# dw08b.net
KiCad netlist of a schematic drawn in EAGLE
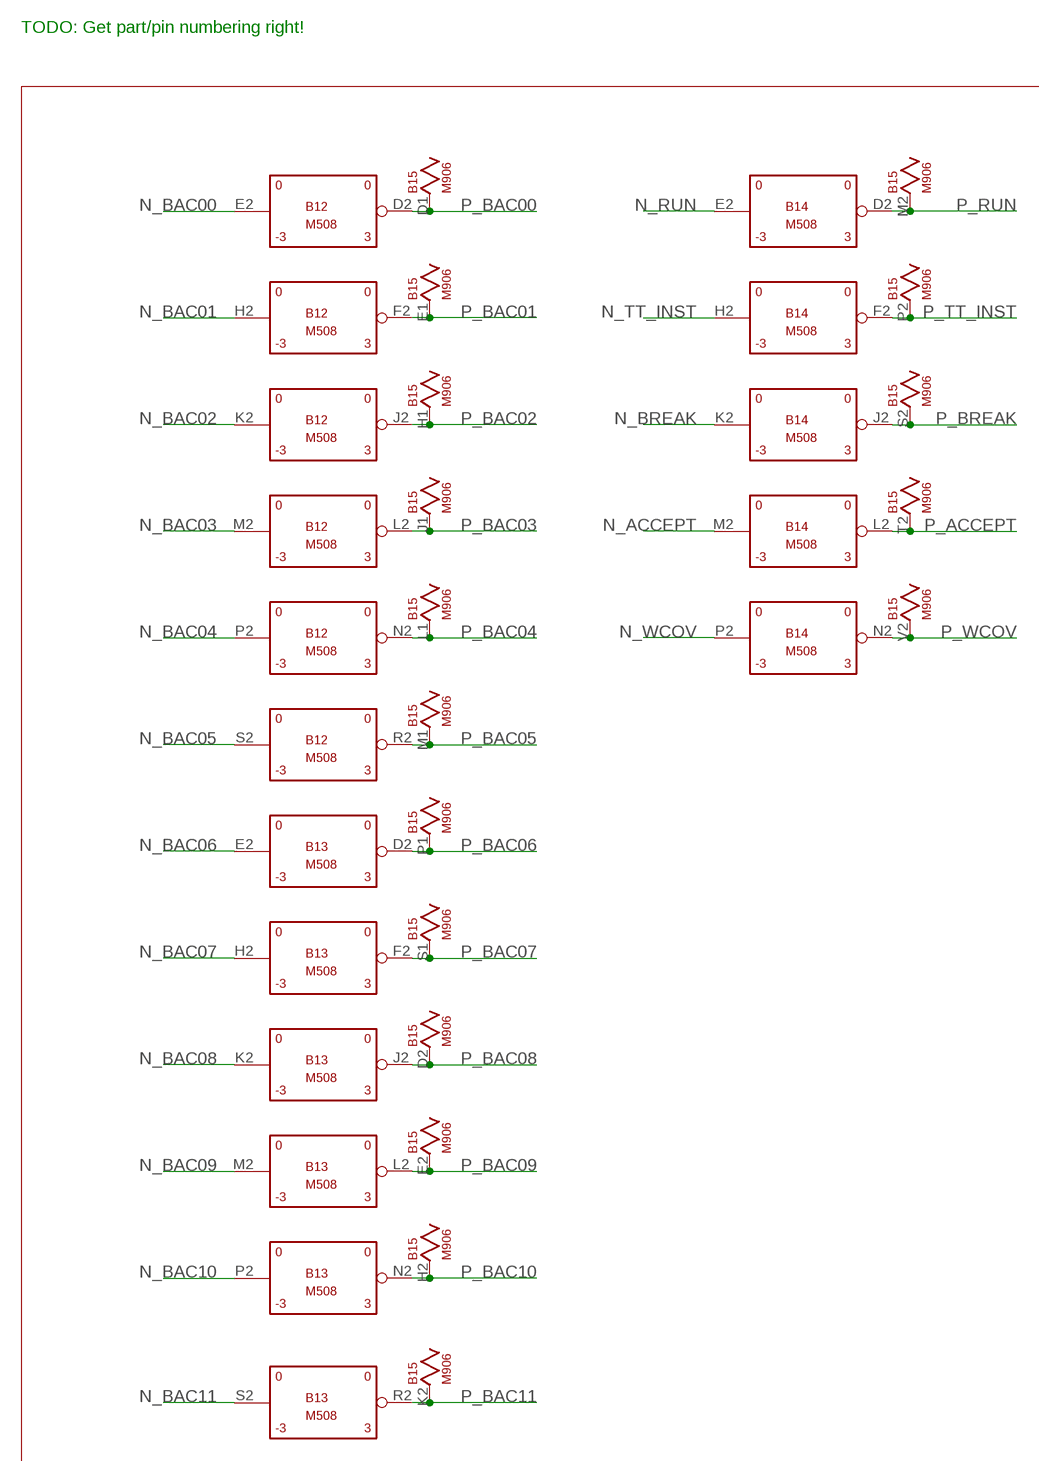
[diagram p0: schematic, sheet 1, part 1 of 2]
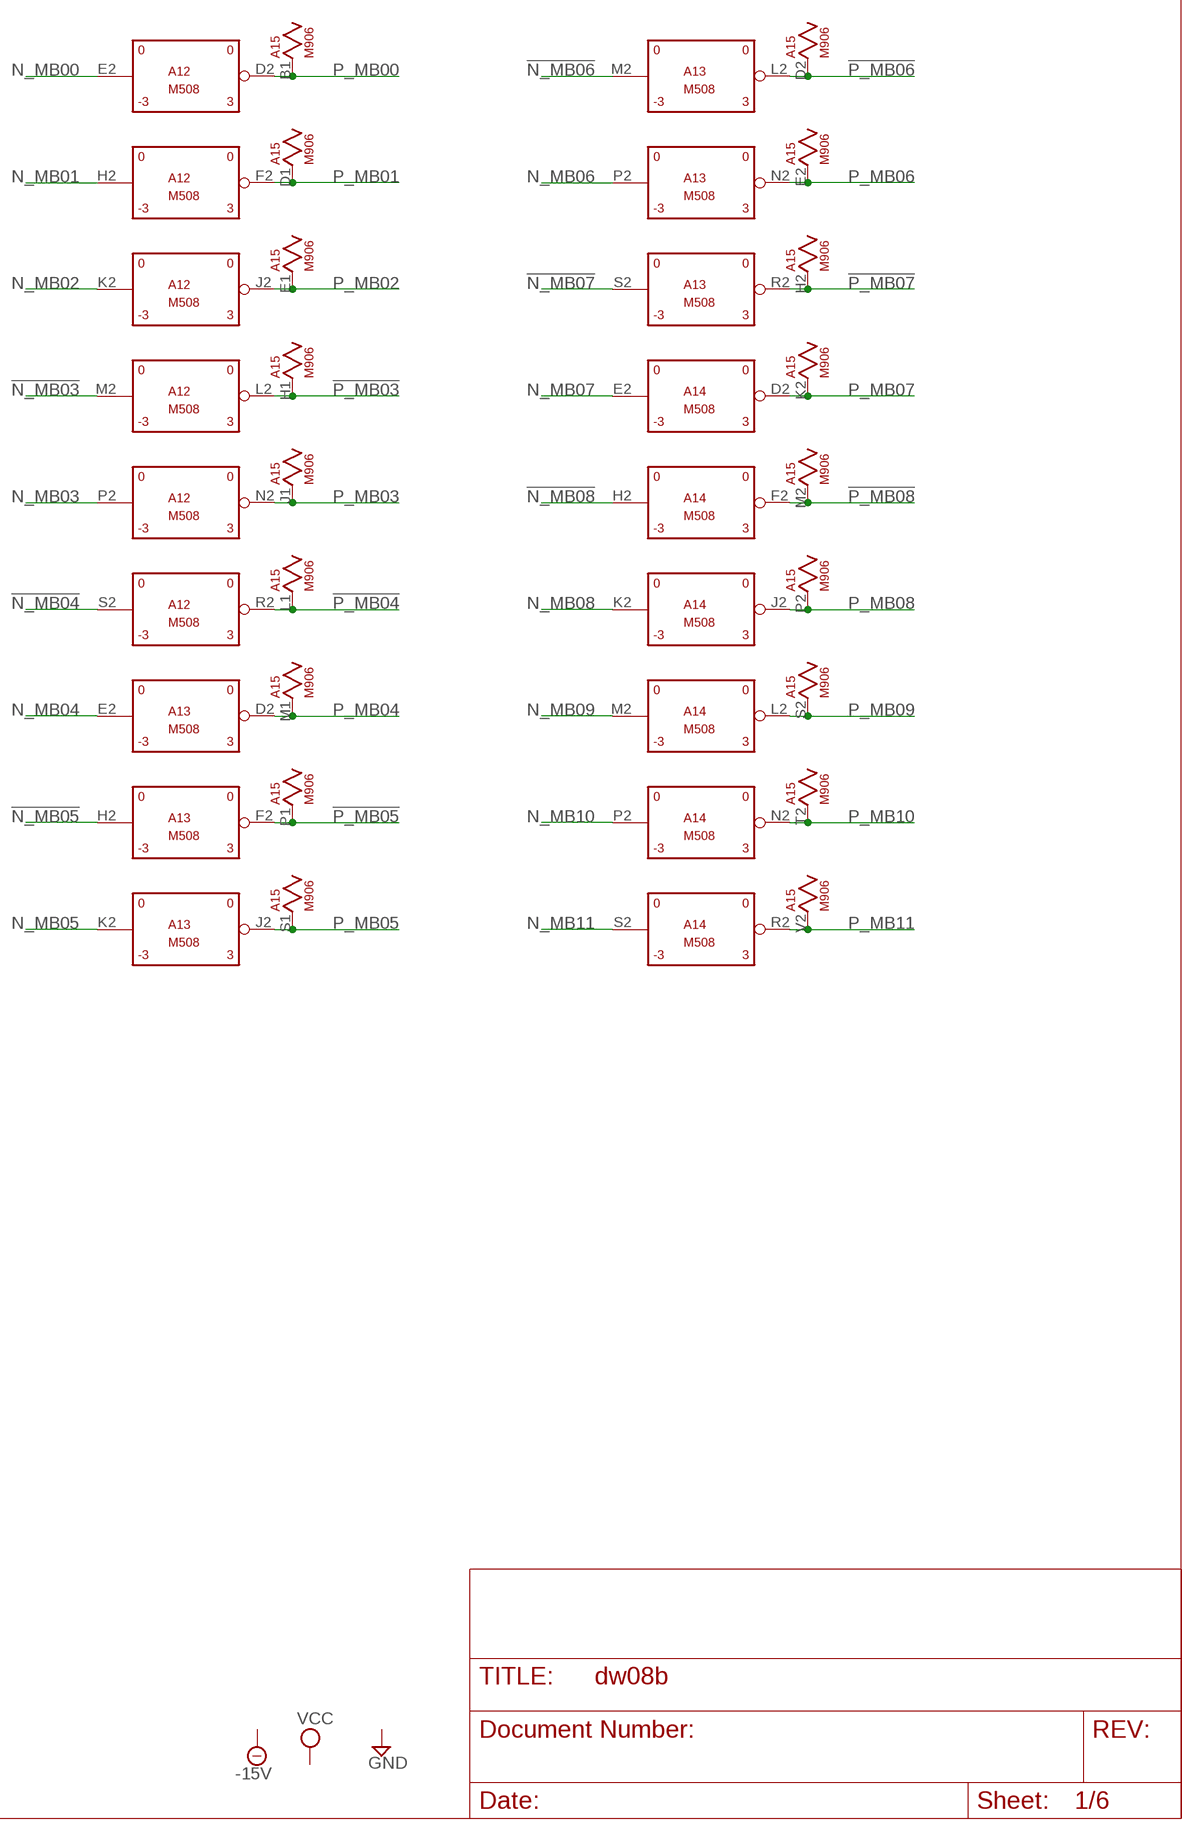
[diagram p1: schematic, sheet 1, part 2 of 2]
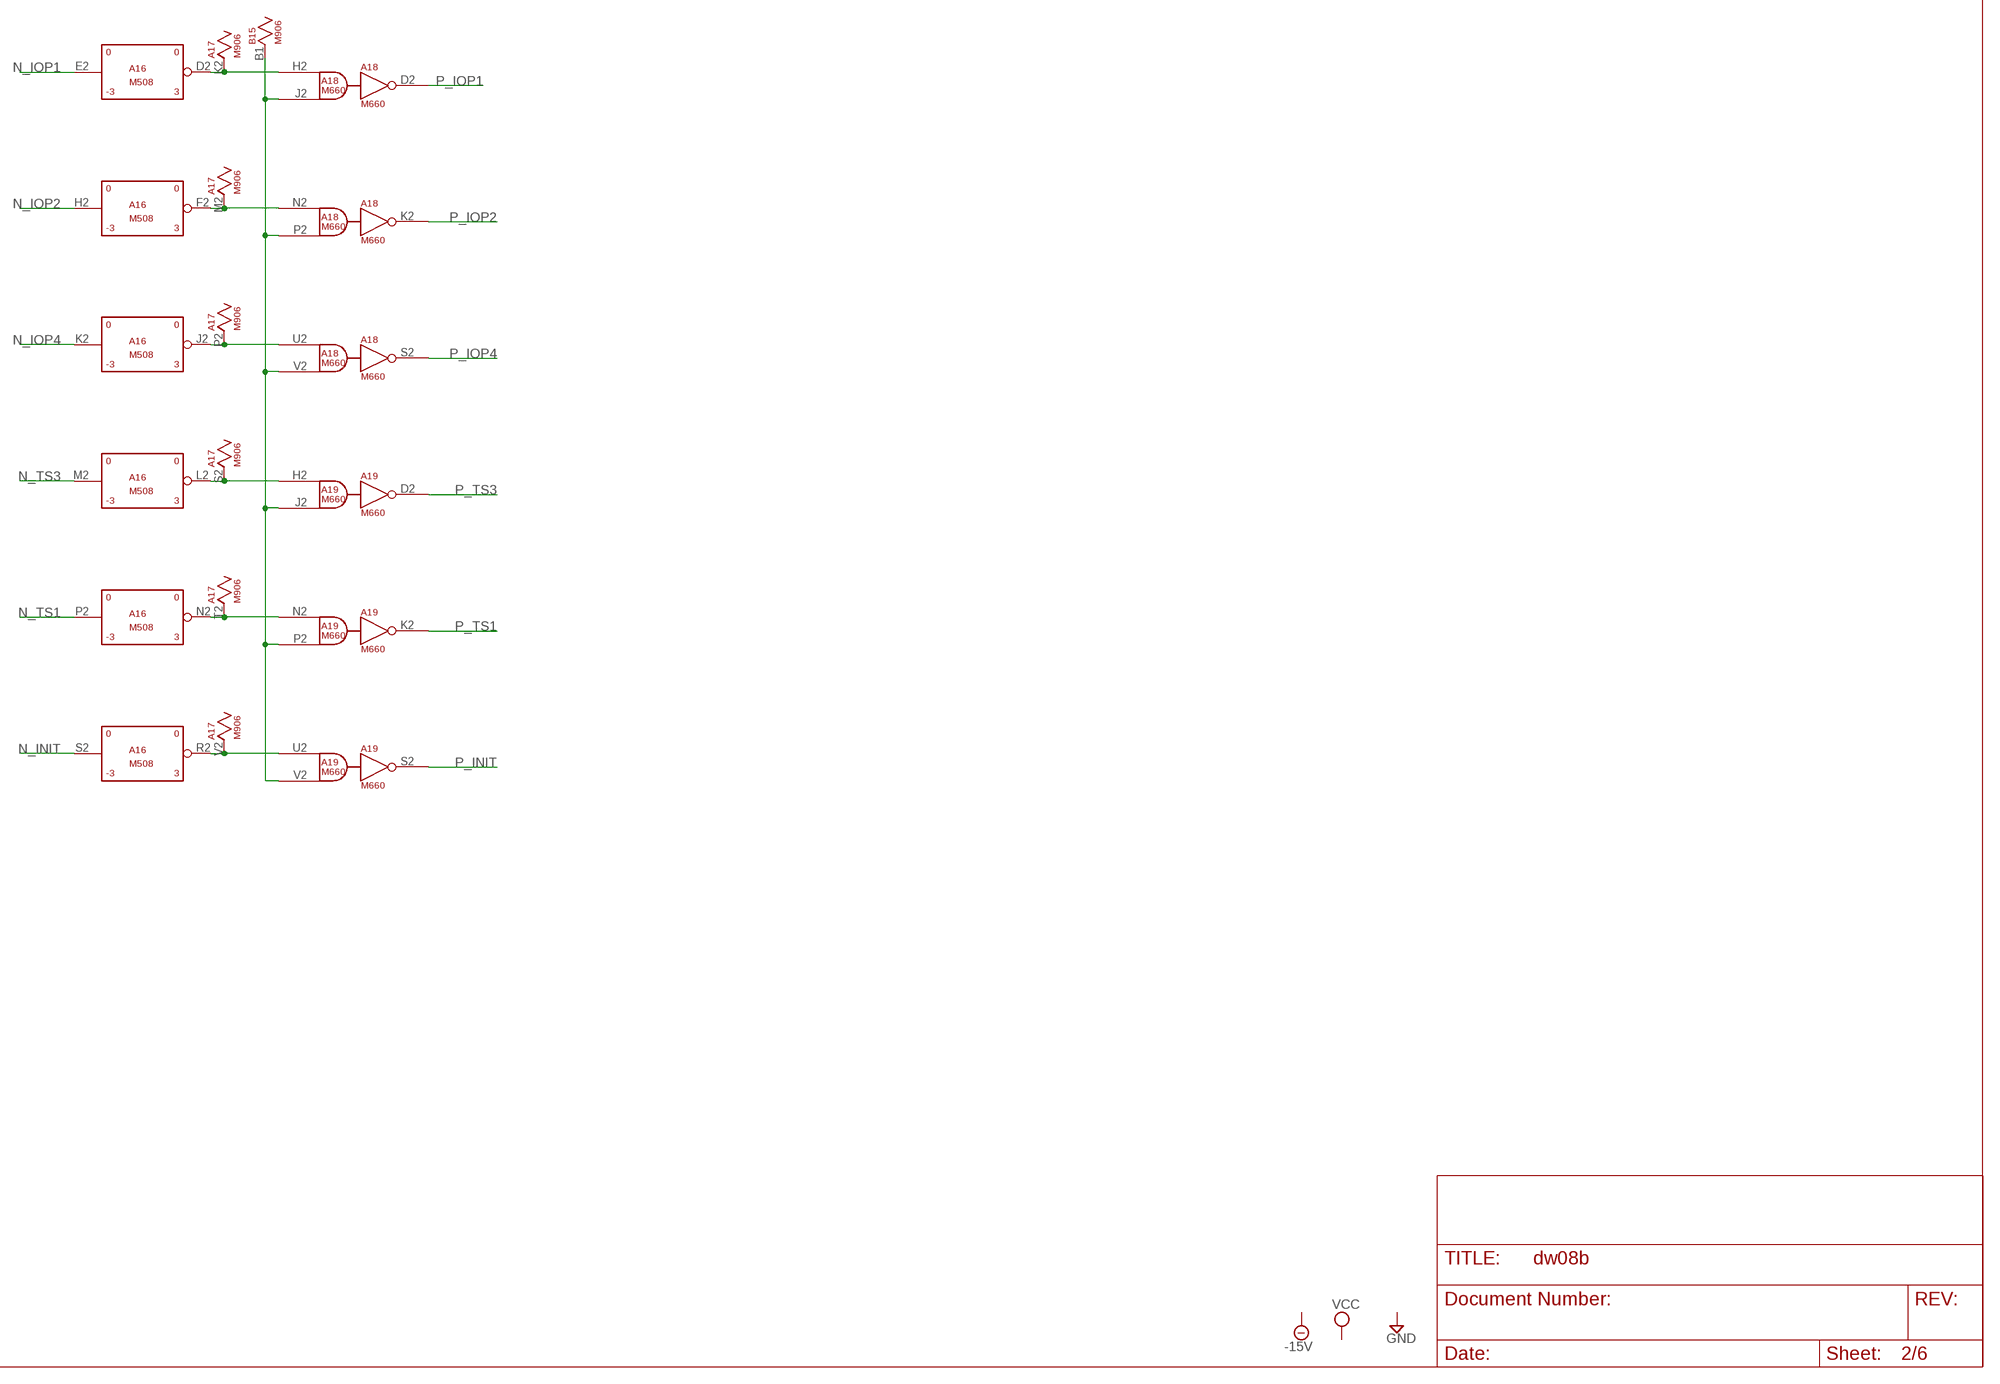
[diagram p2: schematic, sheet 2]
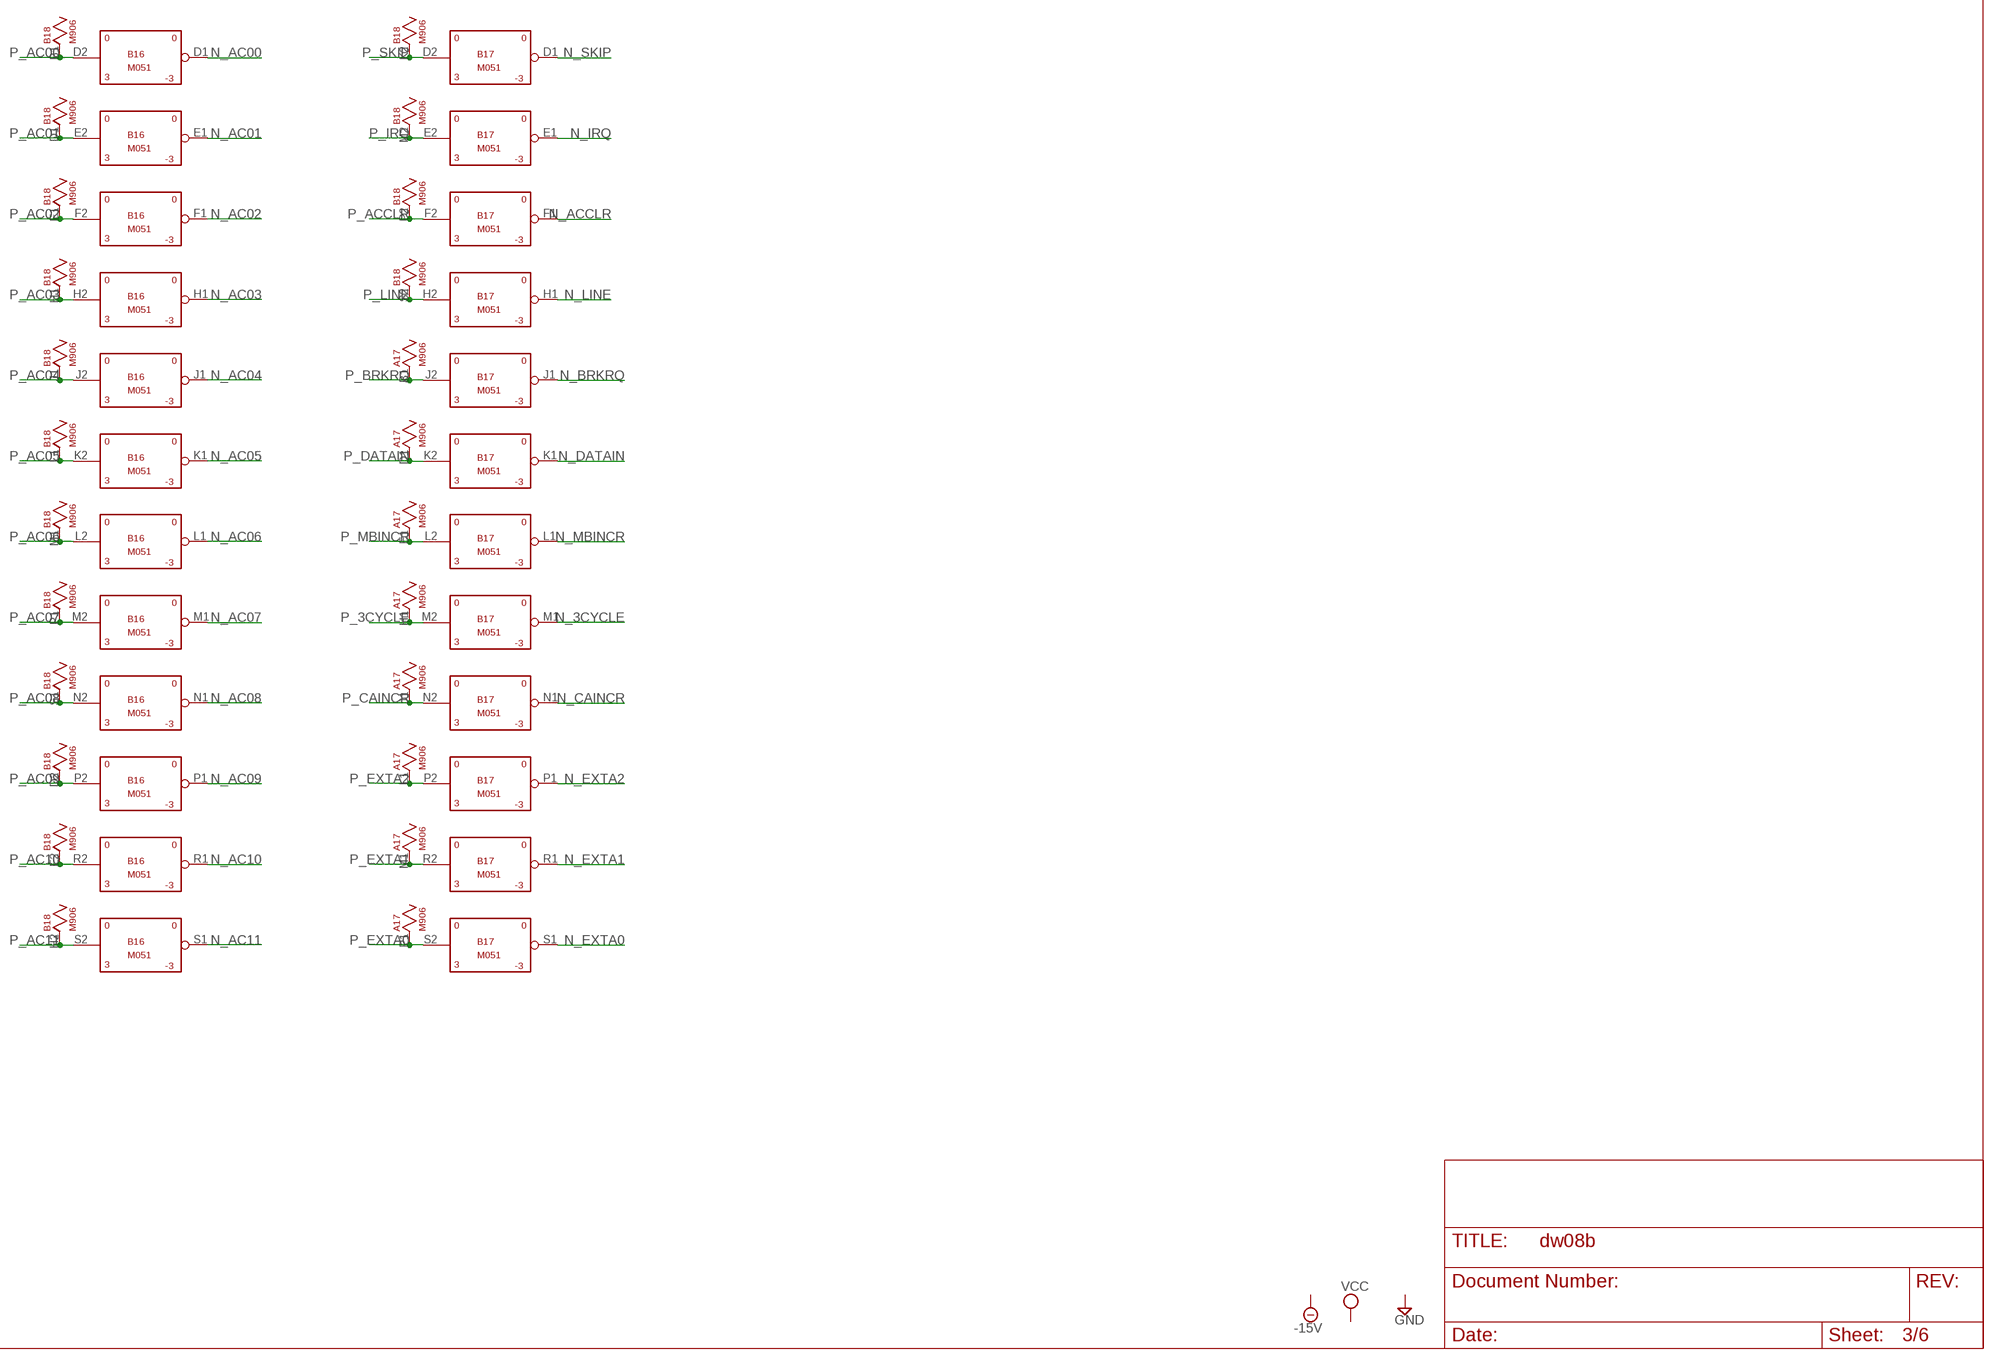
[diagram p3: schematic, sheet 3]
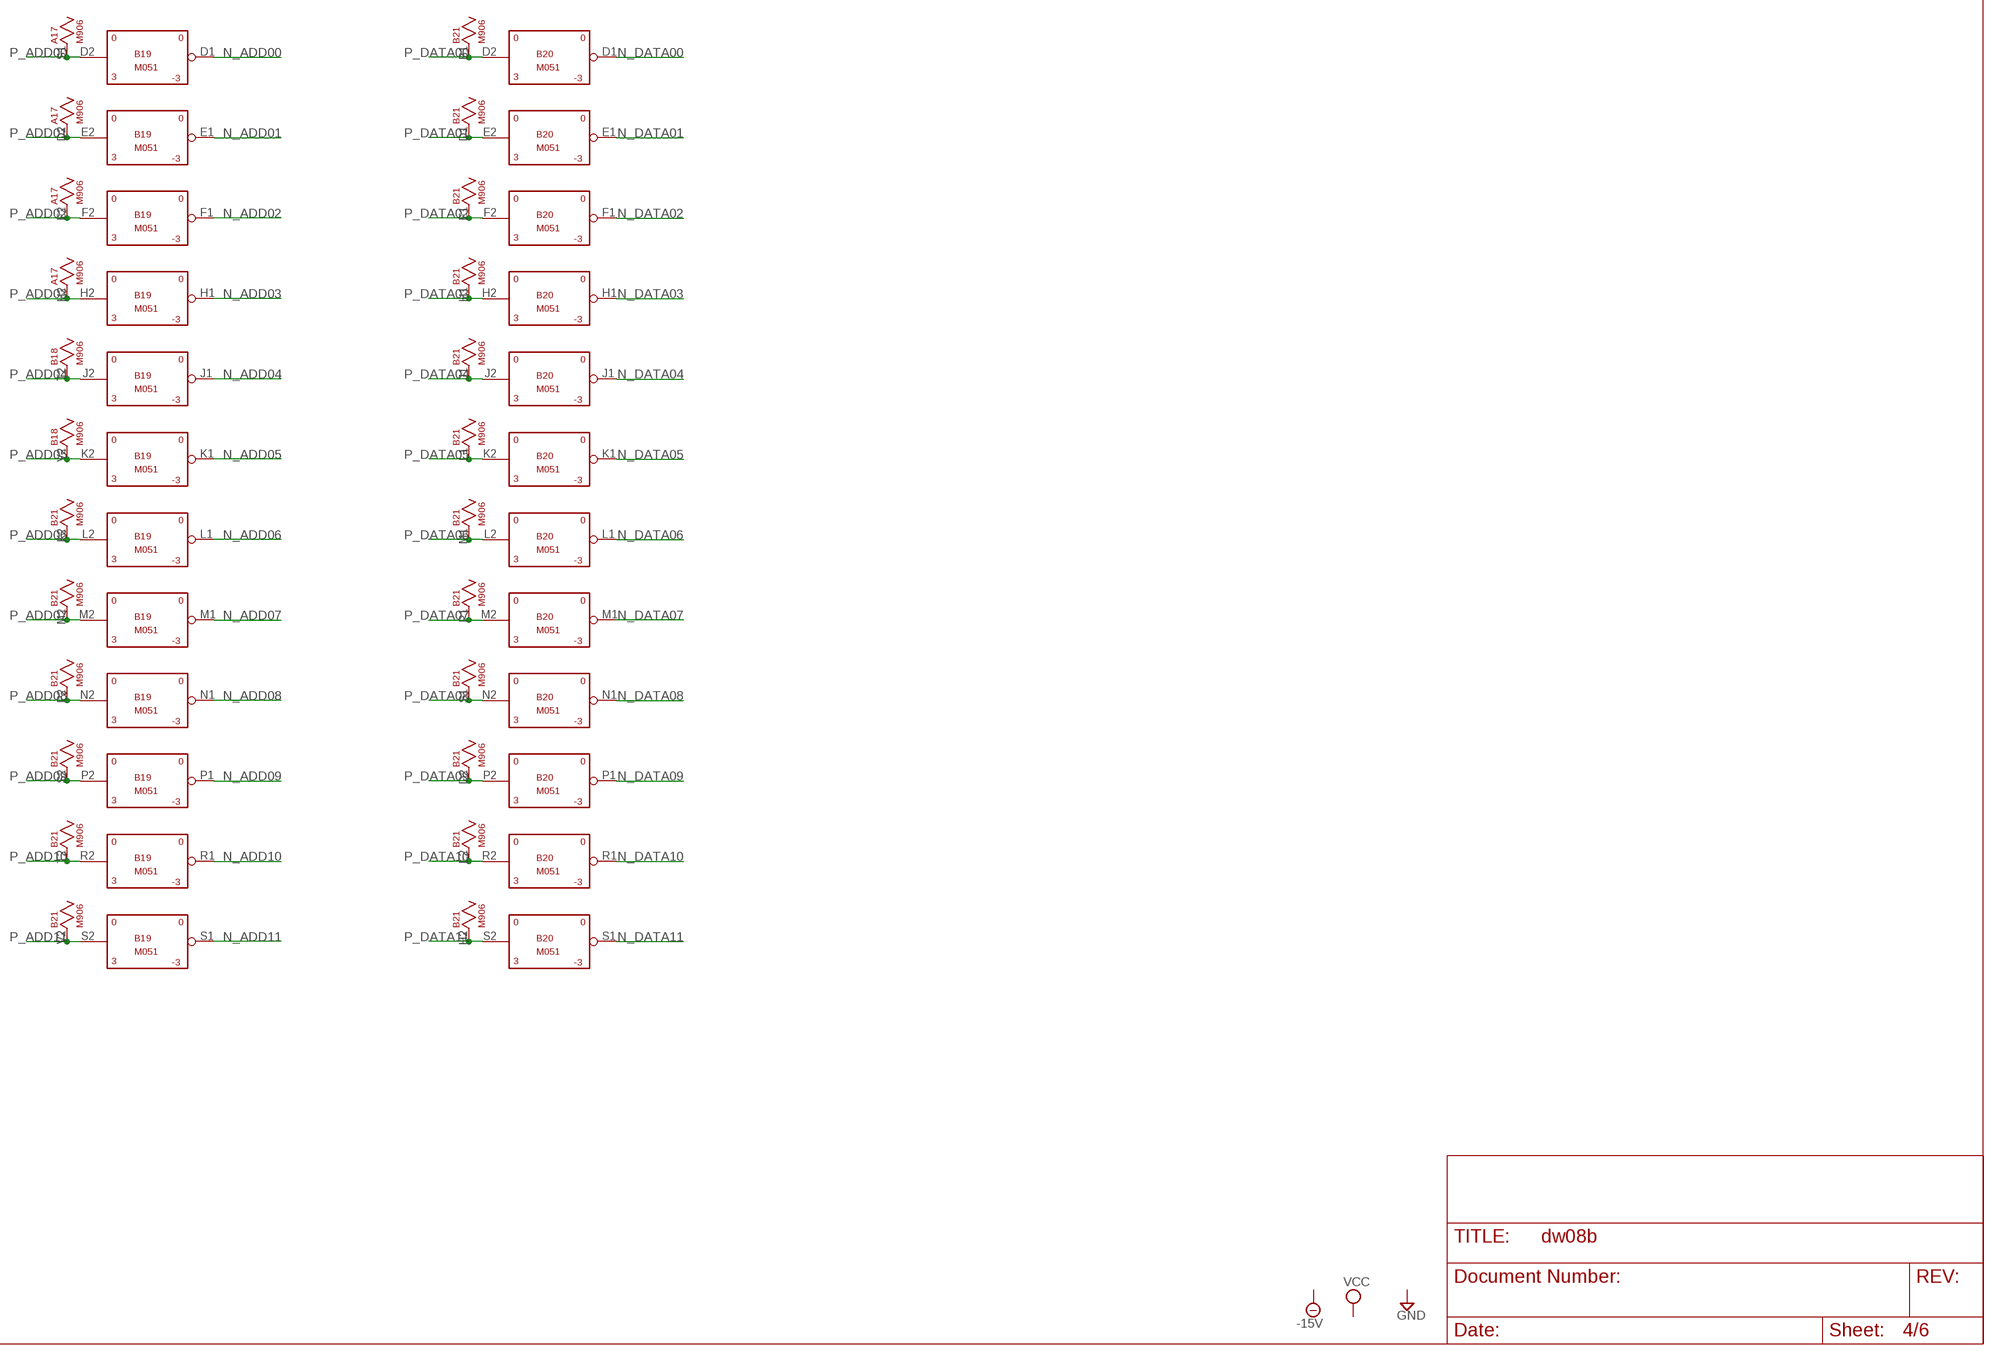
[diagram p4: schematic, sheet 4]
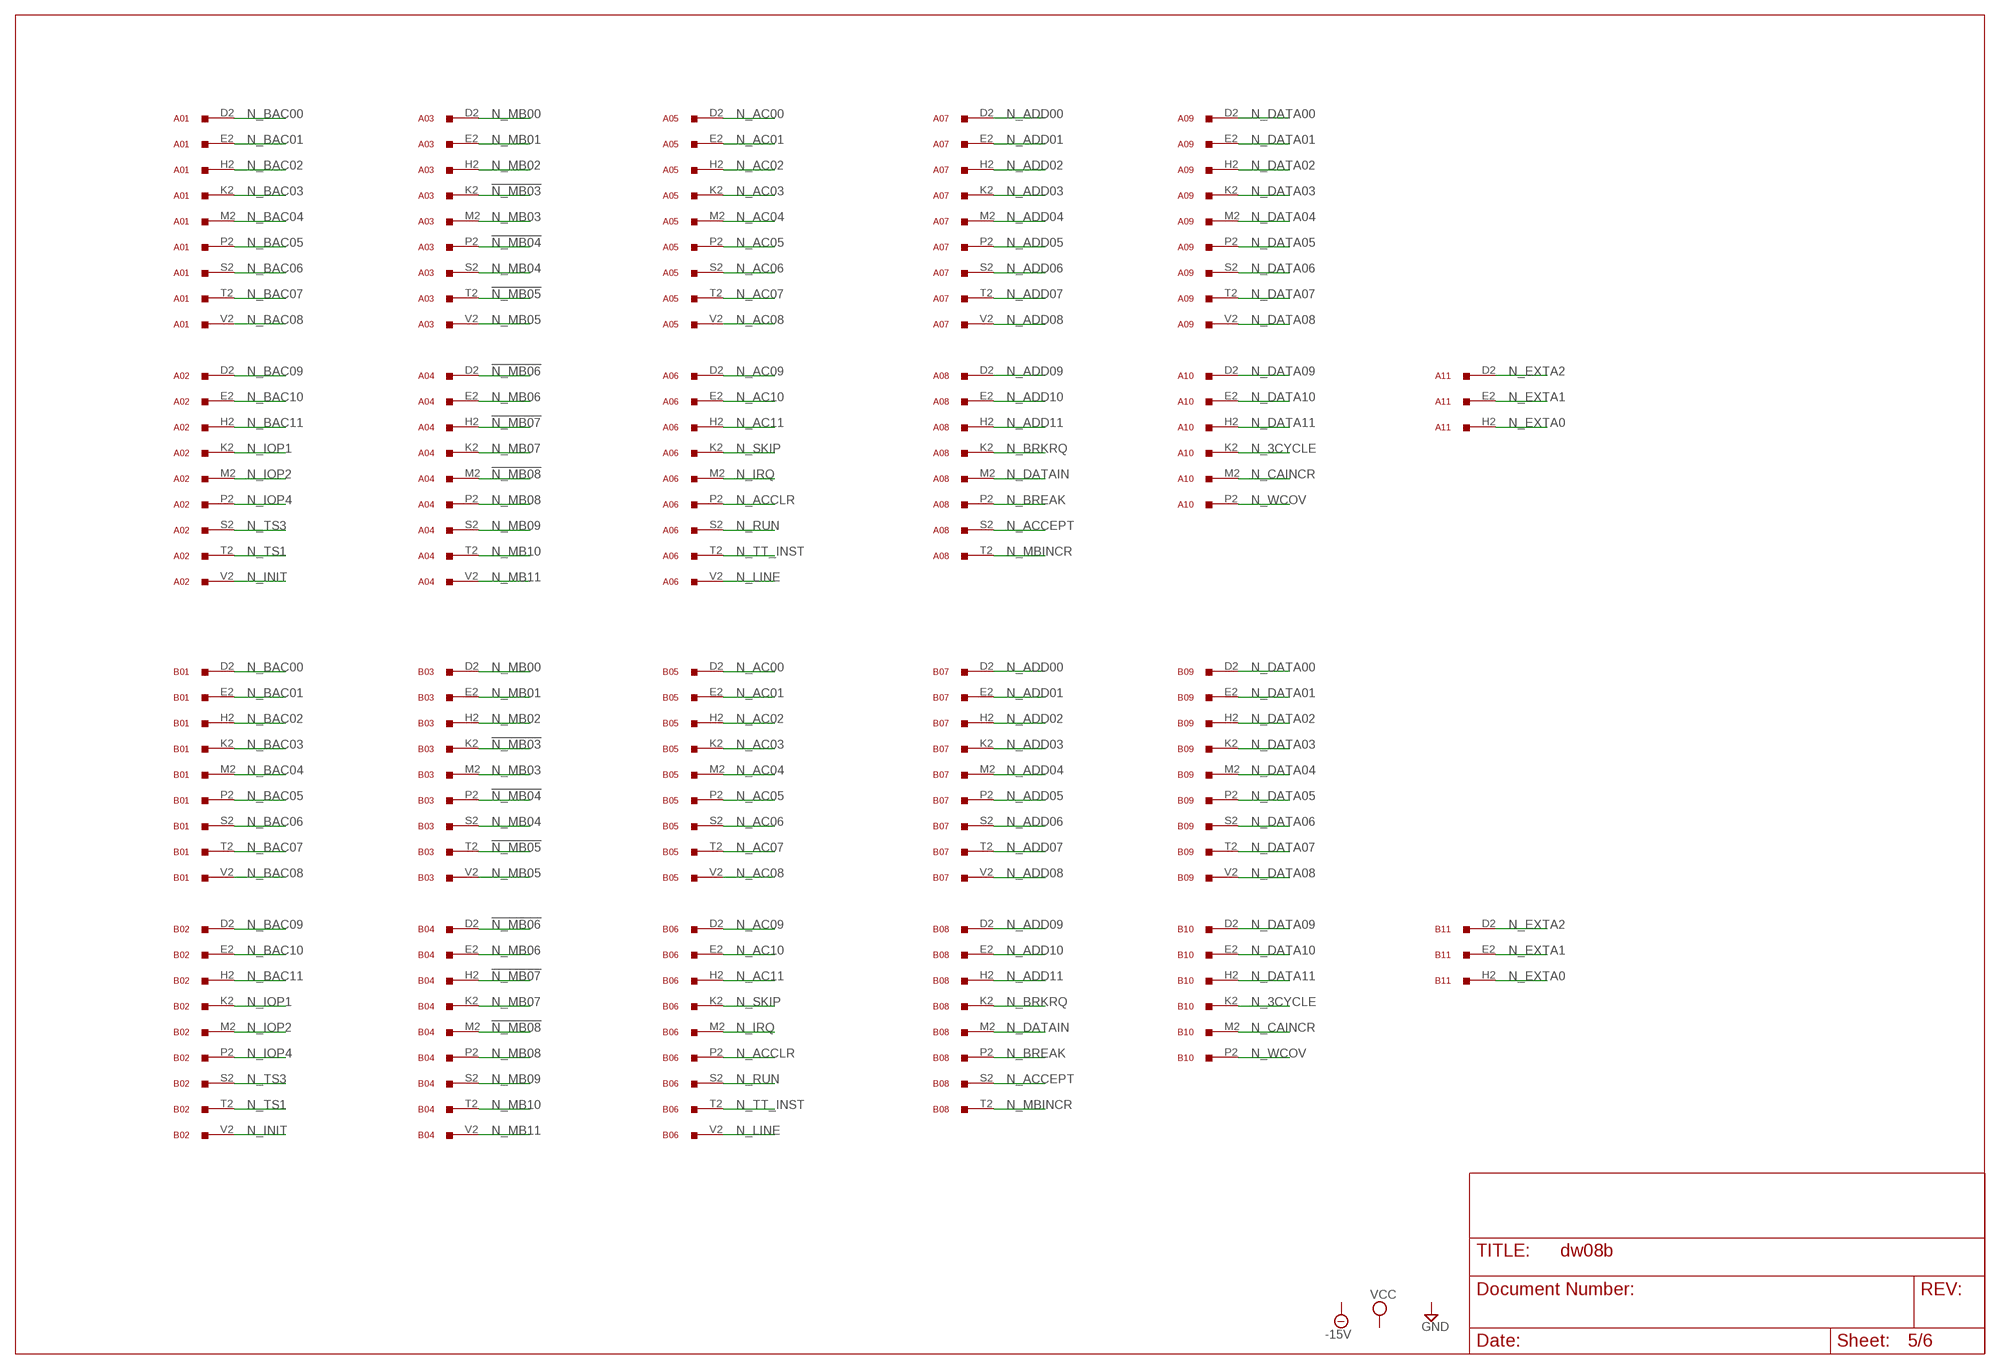
[diagram p5: schematic, sheet 5]
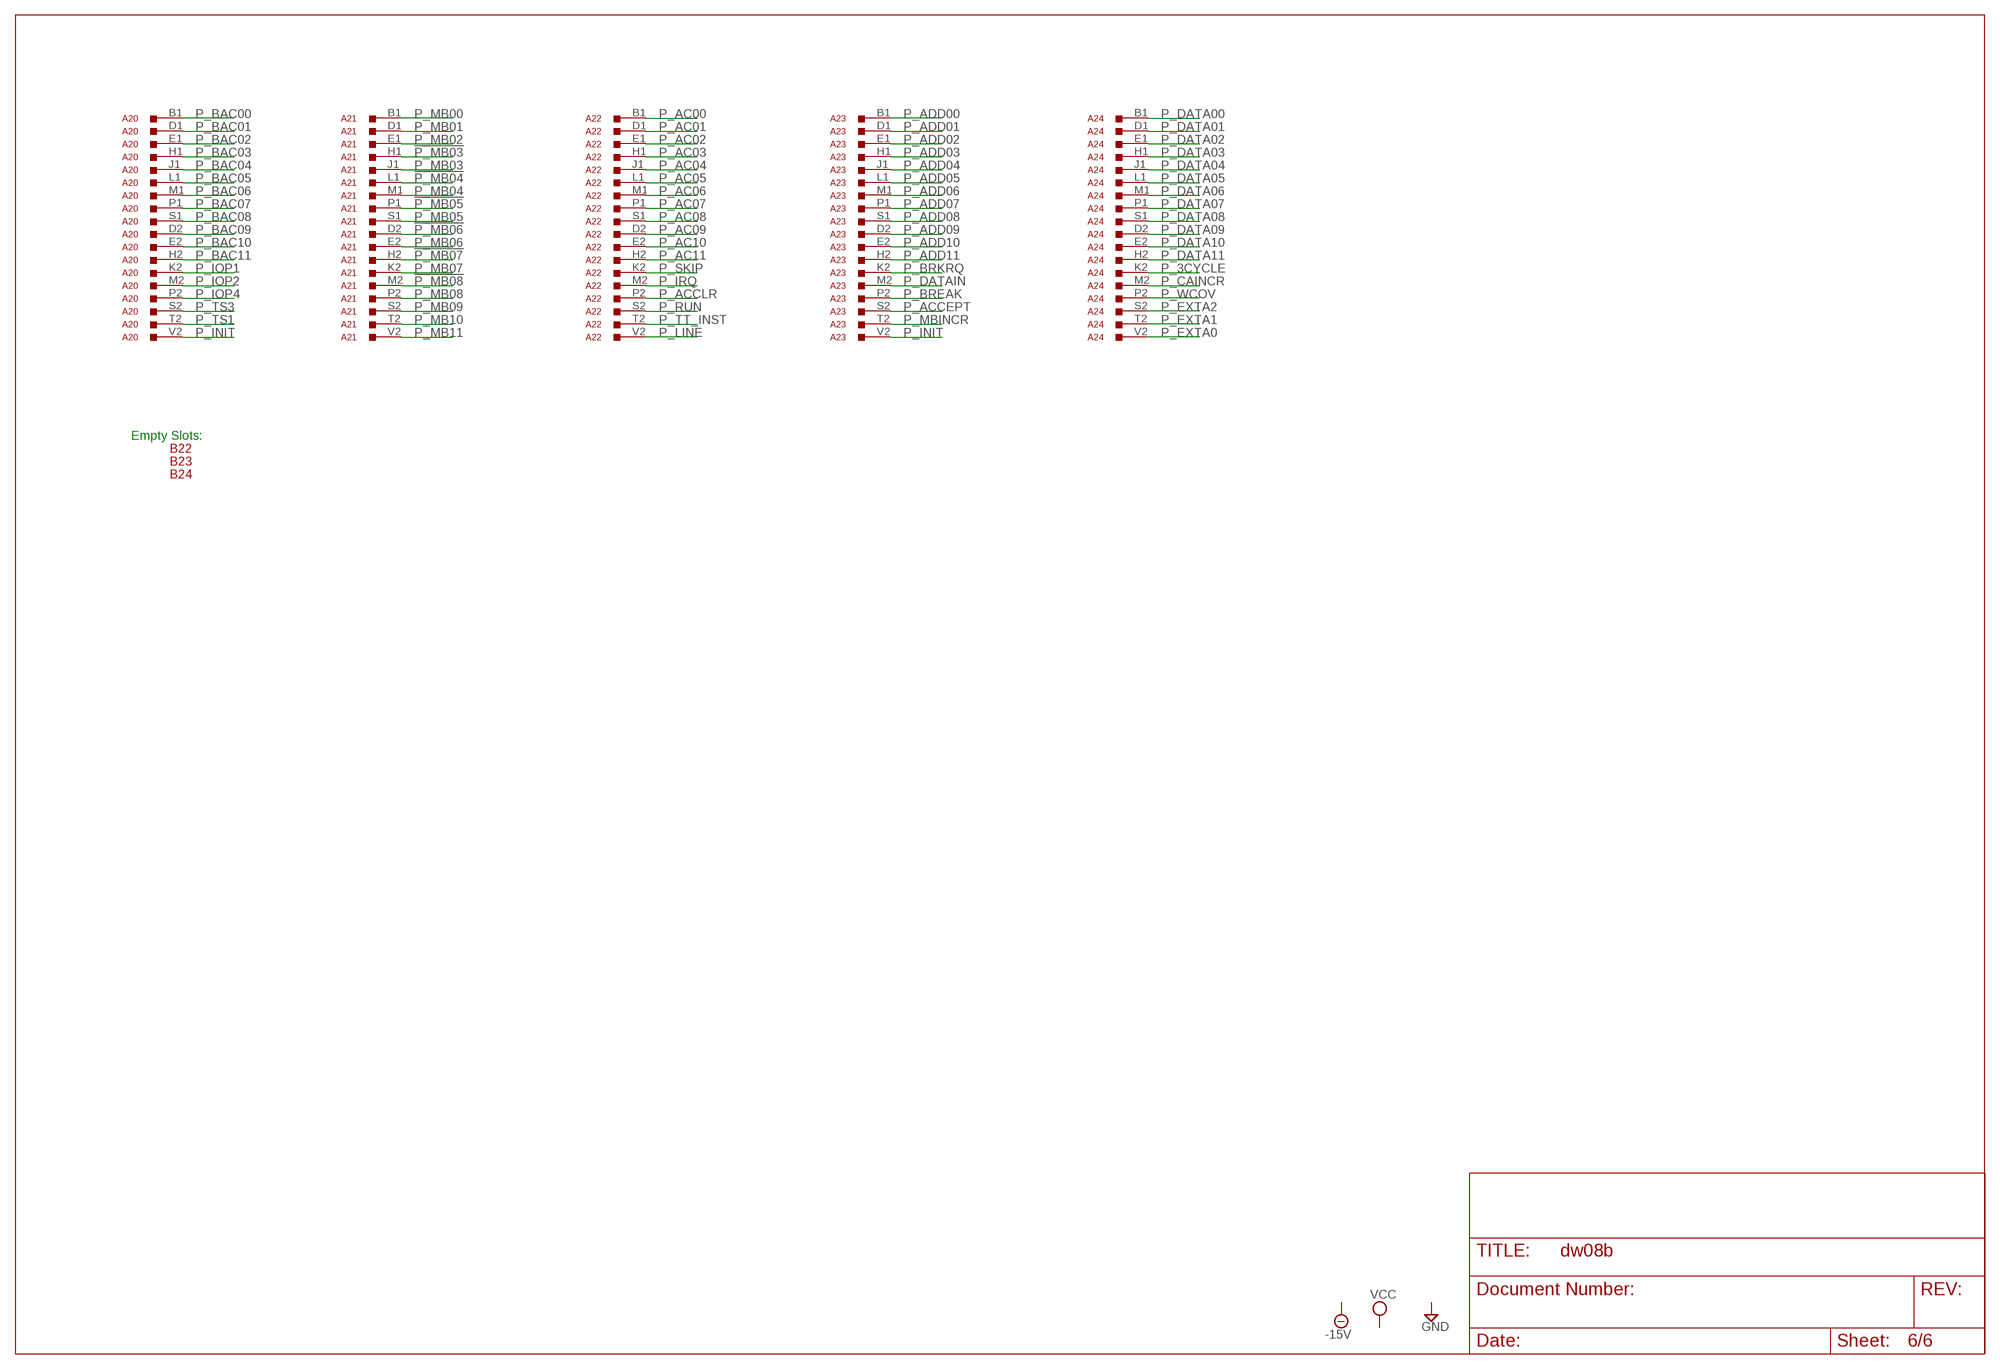
[diagram p6: schematic, sheet 6]

(export (version "E")
  (design (tool "Eeschema 10.0.6"))
  (components
    (comp (ref "A17")
      (value "M906")
      (footprint "eagle-import:H807")
      (libsource (lib "eagle-import") (part "M906"))
    )
    (comp (ref "B18")
      (value "M906")
      (footprint "eagle-import:H807")
      (libsource (lib "eagle-import") (part "M906"))
    )
    (comp (ref "B19")
      (value "M051")
      (footprint "eagle-import:H807")
      (libsource (lib "eagle-import") (part "M051"))
    )
    (comp (ref "B20")
      (value "M051")
      (footprint "eagle-import:H807")
      (libsource (lib "eagle-import") (part "M051"))
    )
    (comp (ref "B21")
      (value "M906")
      (footprint "eagle-import:H807")
      (libsource (lib "eagle-import") (part "M906"))
    )
    (comp (ref "A20")
      (value "M903")
      (footprint "eagle-import:H807")
      (libsource (lib "eagle-import") (part "M903"))
    )
    (comp (ref "A21")
      (value "M903")
      (footprint "eagle-import:H807")
      (libsource (lib "eagle-import") (part "M903"))
    )
    (comp (ref "A22")
      (value "M903")
      (footprint "eagle-import:H807")
      (libsource (lib "eagle-import") (part "M903"))
    )
    (comp (ref "A23")
      (value "M903")
      (footprint "eagle-import:H807")
      (libsource (lib "eagle-import") (part "M903"))
    )
    (comp (ref "A24")
      (value "M903")
      (footprint "eagle-import:H807")
      (libsource (lib "eagle-import") (part "M903"))
    )
    (comp (ref "B22")
      (value "H807")
      (footprint "eagle-import:H807")
      (libsource (lib "eagle-import") (part "H807"))
    )
    (comp (ref "B23")
      (value "H807")
      (footprint "eagle-import:H807")
      (libsource (lib "eagle-import") (part "H807"))
    )
    (comp (ref "B24")
      (value "H807")
      (footprint "eagle-import:H807")
      (libsource (lib "eagle-import") (part "H807"))
    )
    (comp (ref "A01")
      (value "W011")
      (footprint "eagle-import:H807")
      (libsource (lib "eagle-import") (part "W011"))
    )
    (comp (ref "A02")
      (value "W011")
      (footprint "eagle-import:H807")
      (libsource (lib "eagle-import") (part "W011"))
    )
    (comp (ref "A03")
      (value "W011")
      (footprint "eagle-import:H807")
      (libsource (lib "eagle-import") (part "W011"))
    )
    (comp (ref "A04")
      (value "W011")
      (footprint "eagle-import:H807")
      (libsource (lib "eagle-import") (part "W011"))
    )
    (comp (ref "A05")
      (value "W011")
      (footprint "eagle-import:H807")
      (libsource (lib "eagle-import") (part "W011"))
    )
    (comp (ref "A06")
      (value "W011")
      (footprint "eagle-import:H807")
      (libsource (lib "eagle-import") (part "W011"))
    )
    (comp (ref "A07")
      (value "W011")
      (footprint "eagle-import:H807")
      (libsource (lib "eagle-import") (part "W011"))
    )
    (comp (ref "A08")
      (value "W011")
      (footprint "eagle-import:H807")
      (libsource (lib "eagle-import") (part "W011"))
    )
    (comp (ref "A09")
      (value "W011")
      (footprint "eagle-import:H807")
      (libsource (lib "eagle-import") (part "W011"))
    )
    (comp (ref "A10")
      (value "W011")
      (footprint "eagle-import:H807")
      (libsource (lib "eagle-import") (part "W011"))
    )
    (comp (ref "A11")
      (value "W011")
      (footprint "eagle-import:H807")
      (libsource (lib "eagle-import") (part "W011"))
    )
    (comp (ref "B01")
      (value "W011")
      (footprint "eagle-import:H807")
      (libsource (lib "eagle-import") (part "W011"))
    )
    (comp (ref "B02")
      (value "W011")
      (footprint "eagle-import:H807")
      (libsource (lib "eagle-import") (part "W011"))
    )
    (comp (ref "B03")
      (value "W011")
      (footprint "eagle-import:H807")
      (libsource (lib "eagle-import") (part "W011"))
    )
    (comp (ref "B04")
      (value "W011")
      (footprint "eagle-import:H807")
      (libsource (lib "eagle-import") (part "W011"))
    )
    (comp (ref "B05")
      (value "W011")
      (footprint "eagle-import:H807")
      (libsource (lib "eagle-import") (part "W011"))
    )
    (comp (ref "B06")
      (value "W011")
      (footprint "eagle-import:H807")
      (libsource (lib "eagle-import") (part "W011"))
    )
    (comp (ref "B07")
      (value "W011")
      (footprint "eagle-import:H807")
      (libsource (lib "eagle-import") (part "W011"))
    )
    (comp (ref "B08")
      (value "W011")
      (footprint "eagle-import:H807")
      (libsource (lib "eagle-import") (part "W011"))
    )
    (comp (ref "B09")
      (value "W011")
      (footprint "eagle-import:H807")
      (libsource (lib "eagle-import") (part "W011"))
    )
    (comp (ref "B10")
      (value "W011")
      (footprint "eagle-import:H807")
      (libsource (lib "eagle-import") (part "W011"))
    )
    (comp (ref "B11")
      (value "W011")
      (footprint "eagle-import:H807")
      (libsource (lib "eagle-import") (part "W011"))
    )
    (comp (ref "B16")
      (value "M051")
      (footprint "eagle-import:H807")
      (libsource (lib "eagle-import") (part "M051"))
    )
    (comp (ref "B17")
      (value "M051")
      (footprint "eagle-import:H807")
      (libsource (lib "eagle-import") (part "M051"))
    )
    (comp (ref "A12")
      (value "M508")
      (footprint "eagle-import:H807")
      (libsource (lib "eagle-import") (part "M508"))
    )
    (comp (ref "A13")
      (value "M508")
      (footprint "eagle-import:H807")
      (libsource (lib "eagle-import") (part "M508"))
    )
    (comp (ref "A14")
      (value "M508")
      (footprint "eagle-import:H807")
      (libsource (lib "eagle-import") (part "M508"))
    )
    (comp (ref "A15")
      (value "M906")
      (footprint "eagle-import:H807")
      (libsource (lib "eagle-import") (part "M906"))
    )
    (comp (ref "B12")
      (value "M508")
      (footprint "eagle-import:H807")
      (libsource (lib "eagle-import") (part "M508"))
    )
    (comp (ref "B13")
      (value "M508")
      (footprint "eagle-import:H807")
      (libsource (lib "eagle-import") (part "M508"))
    )
    (comp (ref "B14")
      (value "M508")
      (footprint "eagle-import:H807")
      (libsource (lib "eagle-import") (part "M508"))
    )
    (comp (ref "B15")
      (value "M906")
      (footprint "eagle-import:H807")
      (libsource (lib "eagle-import") (part "M906"))
    )
    (comp (ref "A16")
      (value "M508")
      (footprint "eagle-import:H807")
      (libsource (lib "eagle-import") (part "M508"))
    )
    (comp (ref "A18")
      (value "M660")
      (footprint "eagle-import:H807")
      (libsource (lib "eagle-import") (part "M660"))
    )
    (comp (ref "A19")
      (value "M660")
      (footprint "eagle-import:H807")
      (libsource (lib "eagle-import") (part "M660"))
    )
  )
  (nets
    (net (code "3") (name "N_3CYCLE") (class "Default")
      (node (ref "A10") (pin "K2") (pinfunction "P$2_K2") (pintype "bidirectional"))
      (node (ref "B10") (pin "K2") (pinfunction "P$2_K2") (pintype "bidirectional"))
      (node (ref "B17") (pin "M1") (pinfunction "OUT_M1") (pintype "output"))
    )
    (net (code "4") (name "N_AC00") (class "Default")
      (node (ref "A05") (pin "D2") (pinfunction "P$2_D2") (pintype "bidirectional"))
      (node (ref "B05") (pin "D2") (pinfunction "P$2_D2") (pintype "bidirectional"))
      (node (ref "B16") (pin "D1") (pinfunction "OUT_D1") (pintype "output"))
    )
    (net (code "5") (name "N_AC01") (class "Default")
      (node (ref "A05") (pin "E2") (pinfunction "P$2_E2") (pintype "bidirectional"))
      (node (ref "B05") (pin "E2") (pinfunction "P$2_E2") (pintype "bidirectional"))
      (node (ref "B16") (pin "E1") (pinfunction "OUT_E1") (pintype "output"))
    )
    (net (code "6") (name "N_AC02") (class "Default")
      (node (ref "A05") (pin "H2") (pinfunction "P$2_H2") (pintype "bidirectional"))
      (node (ref "B05") (pin "H2") (pinfunction "P$2_H2") (pintype "bidirectional"))
      (node (ref "B16") (pin "F1") (pinfunction "OUT_F1") (pintype "output"))
    )
    (net (code "7") (name "N_AC03") (class "Default")
      (node (ref "A05") (pin "K2") (pinfunction "P$2_K2") (pintype "bidirectional"))
      (node (ref "B05") (pin "K2") (pinfunction "P$2_K2") (pintype "bidirectional"))
      (node (ref "B16") (pin "H1") (pinfunction "OUT_H1") (pintype "output"))
    )
    (net (code "8") (name "N_AC04") (class "Default")
      (node (ref "A05") (pin "M2") (pinfunction "P$2_M2") (pintype "bidirectional"))
      (node (ref "B05") (pin "M2") (pinfunction "P$2_M2") (pintype "bidirectional"))
      (node (ref "B16") (pin "J1") (pinfunction "OUT_J1") (pintype "output"))
    )
    (net (code "9") (name "N_AC05") (class "Default")
      (node (ref "A05") (pin "P2") (pinfunction "P$2_P2") (pintype "bidirectional"))
      (node (ref "B05") (pin "P2") (pinfunction "P$2_P2") (pintype "bidirectional"))
      (node (ref "B16") (pin "K1") (pinfunction "OUT_K1") (pintype "output"))
    )
    (net (code "10") (name "N_AC06") (class "Default")
      (node (ref "A05") (pin "S2") (pinfunction "P$2_S2") (pintype "bidirectional"))
      (node (ref "B05") (pin "S2") (pinfunction "P$2_S2") (pintype "bidirectional"))
      (node (ref "B16") (pin "L1") (pinfunction "OUT_L1") (pintype "output"))
    )
    (net (code "11") (name "N_AC07") (class "Default")
      (node (ref "A05") (pin "T2") (pinfunction "P$2_T2") (pintype "bidirectional"))
      (node (ref "B05") (pin "T2") (pinfunction "P$2_T2") (pintype "bidirectional"))
      (node (ref "B16") (pin "M1") (pinfunction "OUT_M1") (pintype "output"))
    )
    (net (code "12") (name "N_AC08") (class "Default")
      (node (ref "A05") (pin "V2") (pinfunction "P$2_V2") (pintype "bidirectional"))
      (node (ref "B05") (pin "V2") (pinfunction "P$2_V2") (pintype "bidirectional"))
      (node (ref "B16") (pin "N1") (pinfunction "OUT_N1") (pintype "output"))
    )
    (net (code "13") (name "N_AC09") (class "Default")
      (node (ref "A06") (pin "D2") (pinfunction "P$2_D2") (pintype "bidirectional"))
      (node (ref "B06") (pin "D2") (pinfunction "P$2_D2") (pintype "bidirectional"))
      (node (ref "B16") (pin "P1") (pinfunction "OUT_P1") (pintype "output"))
    )
    (net (code "14") (name "N_AC10") (class "Default")
      (node (ref "A06") (pin "E2") (pinfunction "P$2_E2") (pintype "bidirectional"))
      (node (ref "B06") (pin "E2") (pinfunction "P$2_E2") (pintype "bidirectional"))
      (node (ref "B16") (pin "R1") (pinfunction "OUT_R1") (pintype "output"))
    )
    (net (code "15") (name "N_AC11") (class "Default")
      (node (ref "A06") (pin "H2") (pinfunction "P$2_H2") (pintype "bidirectional"))
      (node (ref "B06") (pin "H2") (pinfunction "P$2_H2") (pintype "bidirectional"))
      (node (ref "B16") (pin "S1") (pinfunction "OUT_S1") (pintype "output"))
    )
    (net (code "16") (name "N_ACCEPT") (class "Default")
      (node (ref "A08") (pin "S2") (pinfunction "P$2_S2") (pintype "bidirectional"))
      (node (ref "B08") (pin "S2") (pinfunction "P$2_S2") (pintype "bidirectional"))
      (node (ref "B14") (pin "M2") (pinfunction "IN_M2") (pintype "input"))
    )
    (net (code "17") (name "N_ACCLR") (class "Default")
      (node (ref "A06") (pin "P2") (pinfunction "P$2_P2") (pintype "bidirectional"))
      (node (ref "B06") (pin "P2") (pinfunction "P$2_P2") (pintype "bidirectional"))
      (node (ref "B17") (pin "F1") (pinfunction "OUT_F1") (pintype "output"))
    )
    (net (code "18") (name "N_ADD00") (class "Default")
      (node (ref "A07") (pin "D2") (pinfunction "P$2_D2") (pintype "bidirectional"))
      (node (ref "B07") (pin "D2") (pinfunction "P$2_D2") (pintype "bidirectional"))
      (node (ref "B19") (pin "D1") (pinfunction "OUT_D1") (pintype "output"))
    )
    (net (code "19") (name "N_ADD01") (class "Default")
      (node (ref "A07") (pin "E2") (pinfunction "P$2_E2") (pintype "bidirectional"))
      (node (ref "B07") (pin "E2") (pinfunction "P$2_E2") (pintype "bidirectional"))
      (node (ref "B19") (pin "E1") (pinfunction "OUT_E1") (pintype "output"))
    )
    (net (code "20") (name "N_ADD02") (class "Default")
      (node (ref "A07") (pin "H2") (pinfunction "P$2_H2") (pintype "bidirectional"))
      (node (ref "B07") (pin "H2") (pinfunction "P$2_H2") (pintype "bidirectional"))
      (node (ref "B19") (pin "F1") (pinfunction "OUT_F1") (pintype "output"))
    )
    (net (code "21") (name "N_ADD03") (class "Default")
      (node (ref "A07") (pin "K2") (pinfunction "P$2_K2") (pintype "bidirectional"))
      (node (ref "B07") (pin "K2") (pinfunction "P$2_K2") (pintype "bidirectional"))
      (node (ref "B19") (pin "H1") (pinfunction "OUT_H1") (pintype "output"))
    )
    (net (code "22") (name "N_ADD04") (class "Default")
      (node (ref "A07") (pin "M2") (pinfunction "P$2_M2") (pintype "bidirectional"))
      (node (ref "B07") (pin "M2") (pinfunction "P$2_M2") (pintype "bidirectional"))
      (node (ref "B19") (pin "J1") (pinfunction "OUT_J1") (pintype "output"))
    )
    (net (code "23") (name "N_ADD05") (class "Default")
      (node (ref "A07") (pin "P2") (pinfunction "P$2_P2") (pintype "bidirectional"))
      (node (ref "B07") (pin "P2") (pinfunction "P$2_P2") (pintype "bidirectional"))
      (node (ref "B19") (pin "K1") (pinfunction "OUT_K1") (pintype "output"))
    )
    (net (code "24") (name "N_ADD06") (class "Default")
      (node (ref "A07") (pin "S2") (pinfunction "P$2_S2") (pintype "bidirectional"))
      (node (ref "B07") (pin "S2") (pinfunction "P$2_S2") (pintype "bidirectional"))
      (node (ref "B19") (pin "L1") (pinfunction "OUT_L1") (pintype "output"))
    )
    (net (code "25") (name "N_ADD07") (class "Default")
      (node (ref "A07") (pin "T2") (pinfunction "P$2_T2") (pintype "bidirectional"))
      (node (ref "B07") (pin "T2") (pinfunction "P$2_T2") (pintype "bidirectional"))
      (node (ref "B19") (pin "M1") (pinfunction "OUT_M1") (pintype "output"))
    )
    (net (code "26") (name "N_ADD08") (class "Default")
      (node (ref "A07") (pin "V2") (pinfunction "P$2_V2") (pintype "bidirectional"))
      (node (ref "B07") (pin "V2") (pinfunction "P$2_V2") (pintype "bidirectional"))
      (node (ref "B19") (pin "N1") (pinfunction "OUT_N1") (pintype "output"))
    )
    (net (code "27") (name "N_ADD09") (class "Default")
      (node (ref "A08") (pin "D2") (pinfunction "P$2_D2") (pintype "bidirectional"))
      (node (ref "B08") (pin "D2") (pinfunction "P$2_D2") (pintype "bidirectional"))
      (node (ref "B19") (pin "P1") (pinfunction "OUT_P1") (pintype "output"))
    )
    (net (code "28") (name "N_ADD10") (class "Default")
      (node (ref "A08") (pin "E2") (pinfunction "P$2_E2") (pintype "bidirectional"))
      (node (ref "B08") (pin "E2") (pinfunction "P$2_E2") (pintype "bidirectional"))
      (node (ref "B19") (pin "R1") (pinfunction "OUT_R1") (pintype "output"))
    )
    (net (code "29") (name "N_ADD11") (class "Default")
      (node (ref "A08") (pin "H2") (pinfunction "P$2_H2") (pintype "bidirectional"))
      (node (ref "B08") (pin "H2") (pinfunction "P$2_H2") (pintype "bidirectional"))
      (node (ref "B19") (pin "S1") (pinfunction "OUT_S1") (pintype "output"))
    )
    (net (code "30") (name "N_BAC00") (class "Default")
      (node (ref "A01") (pin "D2") (pinfunction "P$2_D2") (pintype "bidirectional"))
      (node (ref "B01") (pin "D2") (pinfunction "P$2_D2") (pintype "bidirectional"))
      (node (ref "B12") (pin "E2") (pinfunction "IN_E2") (pintype "input"))
    )
    (net (code "31") (name "N_BAC01") (class "Default")
      (node (ref "A01") (pin "E2") (pinfunction "P$2_E2") (pintype "bidirectional"))
      (node (ref "B01") (pin "E2") (pinfunction "P$2_E2") (pintype "bidirectional"))
      (node (ref "B12") (pin "H2") (pinfunction "IN_H2") (pintype "input"))
    )
    (net (code "32") (name "N_BAC02") (class "Default")
      (node (ref "A01") (pin "H2") (pinfunction "P$2_H2") (pintype "bidirectional"))
      (node (ref "B01") (pin "H2") (pinfunction "P$2_H2") (pintype "bidirectional"))
      (node (ref "B12") (pin "K2") (pinfunction "IN_K2") (pintype "input"))
    )
    (net (code "33") (name "N_BAC03") (class "Default")
      (node (ref "A01") (pin "K2") (pinfunction "P$2_K2") (pintype "bidirectional"))
      (node (ref "B01") (pin "K2") (pinfunction "P$2_K2") (pintype "bidirectional"))
      (node (ref "B12") (pin "M2") (pinfunction "IN_M2") (pintype "input"))
    )
    (net (code "34") (name "N_BAC04") (class "Default")
      (node (ref "A01") (pin "M2") (pinfunction "P$2_M2") (pintype "bidirectional"))
      (node (ref "B01") (pin "M2") (pinfunction "P$2_M2") (pintype "bidirectional"))
      (node (ref "B12") (pin "P2") (pinfunction "IN_P2") (pintype "input"))
    )
    (net (code "35") (name "N_BAC05") (class "Default")
      (node (ref "A01") (pin "P2") (pinfunction "P$2_P2") (pintype "bidirectional"))
      (node (ref "B01") (pin "P2") (pinfunction "P$2_P2") (pintype "bidirectional"))
      (node (ref "B12") (pin "S2") (pinfunction "IN_S2") (pintype "input"))
    )
    (net (code "36") (name "N_BAC06") (class "Default")
      (node (ref "A01") (pin "S2") (pinfunction "P$2_S2") (pintype "bidirectional"))
      (node (ref "B01") (pin "S2") (pinfunction "P$2_S2") (pintype "bidirectional"))
      (node (ref "B13") (pin "E2") (pinfunction "IN_E2") (pintype "input"))
    )
    (net (code "37") (name "N_BAC07") (class "Default")
      (node (ref "A01") (pin "T2") (pinfunction "P$2_T2") (pintype "bidirectional"))
      (node (ref "B01") (pin "T2") (pinfunction "P$2_T2") (pintype "bidirectional"))
      (node (ref "B13") (pin "H2") (pinfunction "IN_H2") (pintype "input"))
    )
    (net (code "38") (name "N_BAC08") (class "Default")
      (node (ref "A01") (pin "V2") (pinfunction "P$2_V2") (pintype "bidirectional"))
      (node (ref "B01") (pin "V2") (pinfunction "P$2_V2") (pintype "bidirectional"))
      (node (ref "B13") (pin "K2") (pinfunction "IN_K2") (pintype "input"))
    )
    (net (code "39") (name "N_BAC09") (class "Default")
      (node (ref "A02") (pin "D2") (pinfunction "P$2_D2") (pintype "bidirectional"))
      (node (ref "B02") (pin "D2") (pinfunction "P$2_D2") (pintype "bidirectional"))
      (node (ref "B13") (pin "M2") (pinfunction "IN_M2") (pintype "input"))
    )
    (net (code "40") (name "N_BAC10") (class "Default")
      (node (ref "A02") (pin "E2") (pinfunction "P$2_E2") (pintype "bidirectional"))
      (node (ref "B02") (pin "E2") (pinfunction "P$2_E2") (pintype "bidirectional"))
      (node (ref "B13") (pin "P2") (pinfunction "IN_P2") (pintype "input"))
    )
    (net (code "41") (name "N_BAC11") (class "Default")
      (node (ref "A02") (pin "H2") (pinfunction "P$2_H2") (pintype "bidirectional"))
      (node (ref "B02") (pin "H2") (pinfunction "P$2_H2") (pintype "bidirectional"))
      (node (ref "B13") (pin "S2") (pinfunction "IN_S2") (pintype "input"))
    )
    (net (code "42") (name "N_BREAK") (class "Default")
      (node (ref "A08") (pin "P2") (pinfunction "P$2_P2") (pintype "bidirectional"))
      (node (ref "B08") (pin "P2") (pinfunction "P$2_P2") (pintype "bidirectional"))
      (node (ref "B14") (pin "K2") (pinfunction "IN_K2") (pintype "input"))
    )
    (net (code "43") (name "N_BRKRQ") (class "Default")
      (node (ref "A08") (pin "K2") (pinfunction "P$2_K2") (pintype "bidirectional"))
      (node (ref "B08") (pin "K2") (pinfunction "P$2_K2") (pintype "bidirectional"))
      (node (ref "B17") (pin "J1") (pinfunction "OUT_J1") (pintype "output"))
    )
    (net (code "44") (name "N_CAINCR") (class "Default")
      (node (ref "A10") (pin "M2") (pinfunction "P$2_M2") (pintype "bidirectional"))
      (node (ref "B10") (pin "M2") (pinfunction "P$2_M2") (pintype "bidirectional"))
      (node (ref "B17") (pin "N1") (pinfunction "OUT_N1") (pintype "output"))
    )
    (net (code "45") (name "N_DATA00") (class "Default")
      (node (ref "A09") (pin "D2") (pinfunction "P$2_D2") (pintype "bidirectional"))
      (node (ref "B09") (pin "D2") (pinfunction "P$2_D2") (pintype "bidirectional"))
      (node (ref "B20") (pin "D1") (pinfunction "OUT_D1") (pintype "output"))
    )
    (net (code "46") (name "N_DATA01") (class "Default")
      (node (ref "A09") (pin "E2") (pinfunction "P$2_E2") (pintype "bidirectional"))
      (node (ref "B09") (pin "E2") (pinfunction "P$2_E2") (pintype "bidirectional"))
      (node (ref "B20") (pin "E1") (pinfunction "OUT_E1") (pintype "output"))
    )
    (net (code "47") (name "N_DATA02") (class "Default")
      (node (ref "A09") (pin "H2") (pinfunction "P$2_H2") (pintype "bidirectional"))
      (node (ref "B09") (pin "H2") (pinfunction "P$2_H2") (pintype "bidirectional"))
      (node (ref "B20") (pin "F1") (pinfunction "OUT_F1") (pintype "output"))
    )
    (net (code "48") (name "N_DATA03") (class "Default")
      (node (ref "A09") (pin "K2") (pinfunction "P$2_K2") (pintype "bidirectional"))
      (node (ref "B09") (pin "K2") (pinfunction "P$2_K2") (pintype "bidirectional"))
      (node (ref "B20") (pin "H1") (pinfunction "OUT_H1") (pintype "output"))
    )
    (net (code "49") (name "N_DATA04") (class "Default")
      (node (ref "A09") (pin "M2") (pinfunction "P$2_M2") (pintype "bidirectional"))
      (node (ref "B09") (pin "M2") (pinfunction "P$2_M2") (pintype "bidirectional"))
      (node (ref "B20") (pin "J1") (pinfunction "OUT_J1") (pintype "output"))
    )
    (net (code "50") (name "N_DATA05") (class "Default")
      (node (ref "A09") (pin "P2") (pinfunction "P$2_P2") (pintype "bidirectional"))
      (node (ref "B09") (pin "P2") (pinfunction "P$2_P2") (pintype "bidirectional"))
      (node (ref "B20") (pin "K1") (pinfunction "OUT_K1") (pintype "output"))
    )
    (net (code "51") (name "N_DATA06") (class "Default")
      (node (ref "A09") (pin "S2") (pinfunction "P$2_S2") (pintype "bidirectional"))
      (node (ref "B09") (pin "S2") (pinfunction "P$2_S2") (pintype "bidirectional"))
      (node (ref "B20") (pin "L1") (pinfunction "OUT_L1") (pintype "output"))
    )
    (net (code "52") (name "N_DATA07") (class "Default")
      (node (ref "A09") (pin "T2") (pinfunction "P$2_T2") (pintype "bidirectional"))
      (node (ref "B09") (pin "T2") (pinfunction "P$2_T2") (pintype "bidirectional"))
      (node (ref "B20") (pin "M1") (pinfunction "OUT_M1") (pintype "output"))
    )
    (net (code "53") (name "N_DATA08") (class "Default")
      (node (ref "A09") (pin "V2") (pinfunction "P$2_V2") (pintype "bidirectional"))
      (node (ref "B09") (pin "V2") (pinfunction "P$2_V2") (pintype "bidirectional"))
      (node (ref "B20") (pin "N1") (pinfunction "OUT_N1") (pintype "output"))
    )
    (net (code "54") (name "N_DATA09") (class "Default")
      (node (ref "A10") (pin "D2") (pinfunction "P$2_D2") (pintype "bidirectional"))
      (node (ref "B10") (pin "D2") (pinfunction "P$2_D2") (pintype "bidirectional"))
      (node (ref "B20") (pin "P1") (pinfunction "OUT_P1") (pintype "output"))
    )
    (net (code "55") (name "N_DATA10") (class "Default")
      (node (ref "A10") (pin "E2") (pinfunction "P$2_E2") (pintype "bidirectional"))
      (node (ref "B10") (pin "E2") (pinfunction "P$2_E2") (pintype "bidirectional"))
      (node (ref "B20") (pin "R1") (pinfunction "OUT_R1") (pintype "output"))
    )
    (net (code "56") (name "N_DATA11") (class "Default")
      (node (ref "A10") (pin "H2") (pinfunction "P$2_H2") (pintype "bidirectional"))
      (node (ref "B10") (pin "H2") (pinfunction "P$2_H2") (pintype "bidirectional"))
      (node (ref "B20") (pin "S1") (pinfunction "OUT_S1") (pintype "output"))
    )
    (net (code "57") (name "N_DATAIN") (class "Default")
      (node (ref "A08") (pin "M2") (pinfunction "P$2_M2") (pintype "bidirectional"))
      (node (ref "B08") (pin "M2") (pinfunction "P$2_M2") (pintype "bidirectional"))
      (node (ref "B17") (pin "K1") (pinfunction "OUT_K1") (pintype "output"))
    )
    (net (code "58") (name "N_EXTA0") (class "Default")
      (node (ref "A11") (pin "H2") (pinfunction "P$2_H2") (pintype "bidirectional"))
      (node (ref "B11") (pin "H2") (pinfunction "P$2_H2") (pintype "bidirectional"))
      (node (ref "B17") (pin "S1") (pinfunction "OUT_S1") (pintype "output"))
    )
    (net (code "59") (name "N_EXTA1") (class "Default")
      (node (ref "A11") (pin "E2") (pinfunction "P$2_E2") (pintype "bidirectional"))
      (node (ref "B11") (pin "E2") (pinfunction "P$2_E2") (pintype "bidirectional"))
      (node (ref "B17") (pin "R1") (pinfunction "OUT_R1") (pintype "output"))
    )
    (net (code "60") (name "N_EXTA2") (class "Default")
      (node (ref "A11") (pin "D2") (pinfunction "P$2_D2") (pintype "bidirectional"))
      (node (ref "B11") (pin "D2") (pinfunction "P$2_D2") (pintype "bidirectional"))
      (node (ref "B17") (pin "P1") (pinfunction "OUT_P1") (pintype "output"))
    )
    (net (code "61") (name "N_INIT") (class "Default")
      (node (ref "A02") (pin "V2") (pinfunction "P$2_V2") (pintype "bidirectional"))
      (node (ref "A16") (pin "S2") (pinfunction "IN_S2") (pintype "input"))
      (node (ref "B02") (pin "V2") (pinfunction "P$2_V2") (pintype "bidirectional"))
    )
    (net (code "62") (name "N_IOP1") (class "Default")
      (node (ref "A02") (pin "K2") (pinfunction "P$2_K2") (pintype "bidirectional"))
      (node (ref "A16") (pin "E2") (pinfunction "IN_E2") (pintype "input"))
      (node (ref "B02") (pin "K2") (pinfunction "P$2_K2") (pintype "bidirectional"))
    )
    (net (code "63") (name "N_IOP2") (class "Default")
      (node (ref "A02") (pin "M2") (pinfunction "P$2_M2") (pintype "bidirectional"))
      (node (ref "A16") (pin "H2") (pinfunction "IN_H2") (pintype "input"))
      (node (ref "B02") (pin "M2") (pinfunction "P$2_M2") (pintype "bidirectional"))
    )
    (net (code "64") (name "N_IOP4") (class "Default")
      (node (ref "A02") (pin "P2") (pinfunction "P$2_P2") (pintype "bidirectional"))
      (node (ref "A16") (pin "K2") (pinfunction "IN_K2") (pintype "input"))
      (node (ref "B02") (pin "P2") (pinfunction "P$2_P2") (pintype "bidirectional"))
    )
    (net (code "65") (name "N_IRQ") (class "Default")
      (node (ref "A06") (pin "M2") (pinfunction "P$2_M2") (pintype "bidirectional"))
      (node (ref "B06") (pin "M2") (pinfunction "P$2_M2") (pintype "bidirectional"))
      (node (ref "B17") (pin "E1") (pinfunction "OUT_E1") (pintype "output"))
    )
    (net (code "66") (name "N_LINE") (class "Default")
      (node (ref "A06") (pin "V2") (pinfunction "P$2_V2") (pintype "bidirectional"))
      (node (ref "B06") (pin "V2") (pinfunction "P$2_V2") (pintype "bidirectional"))
      (node (ref "B17") (pin "H1") (pinfunction "OUT_H1") (pintype "output"))
    )
    (net (code "67") (name "N_MB00") (class "Default")
      (node (ref "A03") (pin "D2") (pinfunction "P$2_D2") (pintype "bidirectional"))
      (node (ref "A12") (pin "E2") (pinfunction "IN_E2") (pintype "input"))
      (node (ref "B03") (pin "D2") (pinfunction "P$2_D2") (pintype "bidirectional"))
    )
    (net (code "68") (name "N_MB01") (class "Default")
      (node (ref "A03") (pin "E2") (pinfunction "P$2_E2") (pintype "bidirectional"))
      (node (ref "A12") (pin "H2") (pinfunction "IN_H2") (pintype "input"))
      (node (ref "B03") (pin "E2") (pinfunction "P$2_E2") (pintype "bidirectional"))
    )
    (net (code "69") (name "N_MB02") (class "Default")
      (node (ref "A03") (pin "H2") (pinfunction "P$2_H2") (pintype "bidirectional"))
      (node (ref "A12") (pin "K2") (pinfunction "IN_K2") (pintype "input"))
      (node (ref "B03") (pin "H2") (pinfunction "P$2_H2") (pintype "bidirectional"))
    )
    (net (code "70") (name "N_MB03") (class "Default")
      (node (ref "A03") (pin "M2") (pinfunction "P$2_M2") (pintype "bidirectional"))
      (node (ref "A12") (pin "P2") (pinfunction "IN_P2") (pintype "input"))
      (node (ref "B03") (pin "M2") (pinfunction "P$2_M2") (pintype "bidirectional"))
    )
    (net (code "71") (name "N_MB04") (class "Default")
      (node (ref "A03") (pin "S2") (pinfunction "P$2_S2") (pintype "bidirectional"))
      (node (ref "A13") (pin "E2") (pinfunction "IN_E2") (pintype "input"))
      (node (ref "B03") (pin "S2") (pinfunction "P$2_S2") (pintype "bidirectional"))
    )
    (net (code "72") (name "N_MB05") (class "Default")
      (node (ref "A03") (pin "V2") (pinfunction "P$2_V2") (pintype "bidirectional"))
      (node (ref "A13") (pin "K2") (pinfunction "IN_K2") (pintype "input"))
      (node (ref "B03") (pin "V2") (pinfunction "P$2_V2") (pintype "bidirectional"))
    )
    (net (code "73") (name "N_MB06") (class "Default")
      (node (ref "A04") (pin "E2") (pinfunction "P$2_E2") (pintype "bidirectional"))
      (node (ref "A13") (pin "P2") (pinfunction "IN_P2") (pintype "input"))
      (node (ref "B04") (pin "E2") (pinfunction "P$2_E2") (pintype "bidirectional"))
    )
    (net (code "74") (name "N_MB07") (class "Default")
      (node (ref "A04") (pin "K2") (pinfunction "P$2_K2") (pintype "bidirectional"))
      (node (ref "A14") (pin "E2") (pinfunction "IN_E2") (pintype "input"))
      (node (ref "B04") (pin "K2") (pinfunction "P$2_K2") (pintype "bidirectional"))
    )
    (net (code "75") (name "N_MB08") (class "Default")
      (node (ref "A04") (pin "P2") (pinfunction "P$2_P2") (pintype "bidirectional"))
      (node (ref "A14") (pin "K2") (pinfunction "IN_K2") (pintype "input"))
      (node (ref "B04") (pin "P2") (pinfunction "P$2_P2") (pintype "bidirectional"))
    )
    (net (code "76") (name "N_MB09") (class "Default")
      (node (ref "A04") (pin "S2") (pinfunction "P$2_S2") (pintype "bidirectional"))
      (node (ref "A14") (pin "M2") (pinfunction "IN_M2") (pintype "input"))
      (node (ref "B04") (pin "S2") (pinfunction "P$2_S2") (pintype "bidirectional"))
    )
    (net (code "77") (name "N_MB10") (class "Default")
      (node (ref "A04") (pin "T2") (pinfunction "P$2_T2") (pintype "bidirectional"))
      (node (ref "A14") (pin "P2") (pinfunction "IN_P2") (pintype "input"))
      (node (ref "B04") (pin "T2") (pinfunction "P$2_T2") (pintype "bidirectional"))
    )
    (net (code "78") (name "N_MB11") (class "Default")
      (node (ref "A04") (pin "V2") (pinfunction "P$2_V2") (pintype "bidirectional"))
      (node (ref "A14") (pin "S2") (pinfunction "IN_S2") (pintype "input"))
      (node (ref "B04") (pin "V2") (pinfunction "P$2_V2") (pintype "bidirectional"))
    )
    (net (code "79") (name "N_MBINCR") (class "Default")
      (node (ref "A08") (pin "T2") (pinfunction "P$2_T2") (pintype "bidirectional"))
      (node (ref "B08") (pin "T2") (pinfunction "P$2_T2") (pintype "bidirectional"))
      (node (ref "B17") (pin "L1") (pinfunction "OUT_L1") (pintype "output"))
    )
    (net (code "80") (name "N_RUN") (class "Default")
      (node (ref "A06") (pin "S2") (pinfunction "P$2_S2") (pintype "bidirectional"))
      (node (ref "B06") (pin "S2") (pinfunction "P$2_S2") (pintype "bidirectional"))
      (node (ref "B14") (pin "E2") (pinfunction "IN_E2") (pintype "input"))
    )
    (net (code "81") (name "N_SKIP") (class "Default")
      (node (ref "A06") (pin "K2") (pinfunction "P$2_K2") (pintype "bidirectional"))
      (node (ref "B06") (pin "K2") (pinfunction "P$2_K2") (pintype "bidirectional"))
      (node (ref "B17") (pin "D1") (pinfunction "OUT_D1") (pintype "output"))
    )
    (net (code "82") (name "N_TS1") (class "Default")
      (node (ref "A02") (pin "T2") (pinfunction "P$2_T2") (pintype "bidirectional"))
      (node (ref "A16") (pin "P2") (pinfunction "IN_P2") (pintype "input"))
      (node (ref "B02") (pin "T2") (pinfunction "P$2_T2") (pintype "bidirectional"))
    )
    (net (code "83") (name "N_TS3") (class "Default")
      (node (ref "A02") (pin "S2") (pinfunction "P$2_S2") (pintype "bidirectional"))
      (node (ref "A16") (pin "M2") (pinfunction "IN_M2") (pintype "input"))
      (node (ref "B02") (pin "S2") (pinfunction "P$2_S2") (pintype "bidirectional"))
    )
    (net (code "84") (name "N_TT_INST") (class "Default")
      (node (ref "A06") (pin "T2") (pinfunction "P$2_T2") (pintype "bidirectional"))
      (node (ref "B06") (pin "T2") (pinfunction "P$2_T2") (pintype "bidirectional"))
      (node (ref "B14") (pin "H2") (pinfunction "IN_H2") (pintype "input"))
    )
    (net (code "85") (name "N_WCOV") (class "Default")
      (node (ref "A10") (pin "P2") (pinfunction "P$2_P2") (pintype "bidirectional"))
      (node (ref "B10") (pin "P2") (pinfunction "P$2_P2") (pintype "bidirectional"))
      (node (ref "B14") (pin "P2") (pinfunction "IN_P2") (pintype "input"))
    )
    (net (code "86") (name "Net-(A16A-OUT)") (class "Default")
      (node (ref "A16") (pin "D2") (pinfunction "OUT_D2") (pintype "output"))
      (node (ref "A17") (pin "K2") (pinfunction "P$1_K2") (pintype "passive"))
      (node (ref "A18") (pin "H2") (pinfunction "IN1_H2") (pintype "input"))
    )
    (net (code "87") (name "Net-(A16B-OUT)") (class "Default")
      (node (ref "A16") (pin "F2") (pinfunction "OUT_F2") (pintype "output"))
      (node (ref "A17") (pin "M2") (pinfunction "P$1_M2") (pintype "passive"))
      (node (ref "A18") (pin "N2") (pinfunction "IN1_N2") (pintype "input"))
    )
    (net (code "88") (name "Net-(A16E-OUT)") (class "Default")
      (node (ref "A16") (pin "J2") (pinfunction "OUT_J2") (pintype "output"))
      (node (ref "A17") (pin "P2") (pinfunction "P$1_P2") (pintype "passive"))
      (node (ref "A18") (pin "U2") (pinfunction "IN1_U2") (pintype "input"))
    )
    (net (code "89") (name "Net-(A16F-OUT)") (class "Default")
      (node (ref "A16") (pin "L2") (pinfunction "OUT_L2") (pintype "output"))
      (node (ref "A17") (pin "S2") (pinfunction "P$1_S2") (pintype "passive"))
      (node (ref "A19") (pin "H2") (pinfunction "IN1_H2") (pintype "input"))
    )
    (net (code "90") (name "Net-(A16G-OUT)") (class "Default")
      (node (ref "A16") (pin "N2") (pinfunction "OUT_N2") (pintype "output"))
      (node (ref "A17") (pin "T2") (pinfunction "P$1_T2") (pintype "passive"))
      (node (ref "A19") (pin "N2") (pinfunction "IN1_N2") (pintype "input"))
    )
    (net (code "91") (name "Net-(A16H-OUT)") (class "Default")
      (node (ref "A16") (pin "R2") (pinfunction "OUT_R2") (pintype "output"))
      (node (ref "A17") (pin "V2") (pinfunction "P$1_V2") (pintype "passive"))
      (node (ref "A19") (pin "U2") (pinfunction "IN1_U2") (pintype "input"))
    )
    (net (code "92") (name "Net-(A18A-IN2)") (class "Default")
      (node (ref "A18") (pin "J2") (pinfunction "IN2_J2") (pintype "input"))
      (node (ref "A18") (pin "P2") (pinfunction "IN2_P2") (pintype "input"))
      (node (ref "A18") (pin "V2") (pinfunction "IN2_V2") (pintype "input"))
      (node (ref "A19") (pin "J2") (pinfunction "IN2_J2") (pintype "input"))
      (node (ref "A19") (pin "P2") (pinfunction "IN2_P2") (pintype "input"))
      (node (ref "A19") (pin "V2") (pinfunction "IN2_V2") (pintype "input"))
      (node (ref "B15") (pin "B1") (pinfunction "P$1_B1") (pintype "passive"))
    )
    (net (code "93") (name "P_3CYCLE") (class "Default")
      (node (ref "A17") (pin "H1") (pinfunction "P$1_H1") (pintype "passive"))
      (node (ref "A24") (pin "K2") (pinfunction "P$2_K2") (pintype "bidirectional"))
      (node (ref "B17") (pin "M2") (pinfunction "IN_M2") (pintype "input"))
    )
    (net (code "94") (name "P_AC00") (class "Default")
      (node (ref "A22") (pin "B1") (pinfunction "P$2_B1") (pintype "bidirectional"))
      (node (ref "B16") (pin "D2") (pinfunction "IN_D2") (pintype "input"))
      (node (ref "B18") (pin "B1") (pinfunction "P$1_B1") (pintype "passive"))
    )
    (net (code "95") (name "P_AC01") (class "Default")
      (node (ref "A22") (pin "D1") (pinfunction "P$2_D1") (pintype "bidirectional"))
      (node (ref "B16") (pin "E2") (pinfunction "IN_E2") (pintype "input"))
      (node (ref "B18") (pin "D1") (pinfunction "P$1_D1") (pintype "passive"))
    )
    (net (code "96") (name "P_AC02") (class "Default")
      (node (ref "A22") (pin "E1") (pinfunction "P$2_E1") (pintype "bidirectional"))
      (node (ref "B16") (pin "F2") (pinfunction "IN_F2") (pintype "input"))
      (node (ref "B18") (pin "E1") (pinfunction "P$1_E1") (pintype "passive"))
    )
    (net (code "97") (name "P_AC03") (class "Default")
      (node (ref "A22") (pin "H1") (pinfunction "P$2_H1") (pintype "bidirectional"))
      (node (ref "B16") (pin "H2") (pinfunction "IN_H2") (pintype "input"))
      (node (ref "B18") (pin "H1") (pinfunction "P$1_H1") (pintype "passive"))
    )
    (net (code "98") (name "P_AC04") (class "Default")
      (node (ref "A22") (pin "J1") (pinfunction "P$2_J1") (pintype "bidirectional"))
      (node (ref "B16") (pin "J2") (pinfunction "IN_J2") (pintype "input"))
      (node (ref "B18") (pin "J1") (pinfunction "P$1_J1") (pintype "passive"))
    )
    (net (code "99") (name "P_AC05") (class "Default")
      (node (ref "A22") (pin "L1") (pinfunction "P$2_L1") (pintype "bidirectional"))
      (node (ref "B16") (pin "K2") (pinfunction "IN_K2") (pintype "input"))
      (node (ref "B18") (pin "L1") (pinfunction "P$1_L1") (pintype "passive"))
    )
    (net (code "100") (name "P_AC06") (class "Default")
      (node (ref "A22") (pin "M1") (pinfunction "P$2_M1") (pintype "bidirectional"))
      (node (ref "B16") (pin "L2") (pinfunction "IN_L2") (pintype "input"))
      (node (ref "B18") (pin "M1") (pinfunction "P$1_M1") (pintype "passive"))
    )
    (net (code "101") (name "P_AC07") (class "Default")
      (node (ref "A22") (pin "P1") (pinfunction "P$2_P1") (pintype "bidirectional"))
      (node (ref "B16") (pin "M2") (pinfunction "IN_M2") (pintype "input"))
      (node (ref "B18") (pin "P1") (pinfunction "P$1_P1") (pintype "passive"))
    )
    (net (code "102") (name "P_AC08") (class "Default")
      (node (ref "A22") (pin "S1") (pinfunction "P$2_S1") (pintype "bidirectional"))
      (node (ref "B16") (pin "N2") (pinfunction "IN_N2") (pintype "input"))
      (node (ref "B18") (pin "S1") (pinfunction "P$1_S1") (pintype "passive"))
    )
    (net (code "103") (name "P_AC09") (class "Default")
      (node (ref "A22") (pin "D2") (pinfunction "P$2_D2") (pintype "bidirectional"))
      (node (ref "B16") (pin "P2") (pinfunction "IN_P2") (pintype "input"))
      (node (ref "B18") (pin "D2") (pinfunction "P$1_D2") (pintype "passive"))
    )
    (net (code "104") (name "P_AC10") (class "Default")
      (node (ref "A22") (pin "E2") (pinfunction "P$2_E2") (pintype "bidirectional"))
      (node (ref "B16") (pin "R2") (pinfunction "IN_R2") (pintype "input"))
      (node (ref "B18") (pin "E2") (pinfunction "P$1_E2") (pintype "passive"))
    )
    (net (code "105") (name "P_AC11") (class "Default")
      (node (ref "A22") (pin "H2") (pinfunction "P$2_H2") (pintype "bidirectional"))
      (node (ref "B16") (pin "S2") (pinfunction "IN_S2") (pintype "input"))
      (node (ref "B18") (pin "H2") (pinfunction "P$1_H2") (pintype "passive"))
    )
    (net (code "106") (name "P_ACCEPT") (class "Default")
      (node (ref "A23") (pin "S2") (pinfunction "P$2_S2") (pintype "bidirectional"))
      (node (ref "B14") (pin "L2") (pinfunction "OUT_L2") (pintype "output"))
      (node (ref "B15") (pin "T2") (pinfunction "P$1_T2") (pintype "passive"))
    )
    (net (code "107") (name "P_ACCLR") (class "Default")
      (node (ref "A22") (pin "P2") (pinfunction "P$2_P2") (pintype "bidirectional"))
      (node (ref "B17") (pin "F2") (pinfunction "IN_F2") (pintype "input"))
      (node (ref "B18") (pin "P2") (pinfunction "P$1_P2") (pintype "passive"))
    )
    (net (code "108") (name "P_ADD00") (class "Default")
      (node (ref "A17") (pin "S1") (pinfunction "P$1_S1") (pintype "passive"))
      (node (ref "A23") (pin "B1") (pinfunction "P$2_B1") (pintype "bidirectional"))
      (node (ref "B19") (pin "D2") (pinfunction "IN_D2") (pintype "input"))
    )
    (net (code "109") (name "P_ADD01") (class "Default")
      (node (ref "A17") (pin "D2") (pinfunction "P$1_D2") (pintype "passive"))
      (node (ref "A23") (pin "D1") (pinfunction "P$2_D1") (pintype "bidirectional"))
      (node (ref "B19") (pin "E2") (pinfunction "IN_E2") (pintype "input"))
    )
    (net (code "110") (name "P_ADD02") (class "Default")
      (node (ref "A17") (pin "E2") (pinfunction "P$1_E2") (pintype "passive"))
      (node (ref "A23") (pin "E1") (pinfunction "P$2_E1") (pintype "bidirectional"))
      (node (ref "B19") (pin "F2") (pinfunction "IN_F2") (pintype "input"))
    )
    (net (code "111") (name "P_ADD03") (class "Default")
      (node (ref "A17") (pin "H2") (pinfunction "P$1_H2") (pintype "passive"))
      (node (ref "A23") (pin "H1") (pinfunction "P$2_H1") (pintype "bidirectional"))
      (node (ref "B19") (pin "H2") (pinfunction "IN_H2") (pintype "input"))
    )
    (net (code "112") (name "P_ADD04") (class "Default")
      (node (ref "A23") (pin "J1") (pinfunction "P$2_J1") (pintype "bidirectional"))
      (node (ref "B18") (pin "T2") (pinfunction "P$1_T2") (pintype "passive"))
      (node (ref "B19") (pin "J2") (pinfunction "IN_J2") (pintype "input"))
    )
    (net (code "113") (name "P_ADD05") (class "Default")
      (node (ref "A23") (pin "L1") (pinfunction "P$2_L1") (pintype "bidirectional"))
      (node (ref "B18") (pin "V2") (pinfunction "P$1_V2") (pintype "passive"))
      (node (ref "B19") (pin "K2") (pinfunction "IN_K2") (pintype "input"))
    )
    (net (code "114") (name "P_ADD06") (class "Default")
      (node (ref "A23") (pin "M1") (pinfunction "P$2_M1") (pintype "bidirectional"))
      (node (ref "B19") (pin "L2") (pinfunction "IN_L2") (pintype "input"))
      (node (ref "B21") (pin "K2") (pinfunction "P$1_K2") (pintype "passive"))
    )
    (net (code "115") (name "P_ADD07") (class "Default")
      (node (ref "A23") (pin "P1") (pinfunction "P$2_P1") (pintype "bidirectional"))
      (node (ref "B19") (pin "M2") (pinfunction "IN_M2") (pintype "input"))
      (node (ref "B21") (pin "M2") (pinfunction "P$1_M2") (pintype "passive"))
    )
    (net (code "116") (name "P_ADD08") (class "Default")
      (node (ref "A23") (pin "S1") (pinfunction "P$2_S1") (pintype "bidirectional"))
      (node (ref "B19") (pin "N2") (pinfunction "IN_N2") (pintype "input"))
      (node (ref "B21") (pin "P2") (pinfunction "P$1_P2") (pintype "passive"))
    )
    (net (code "117") (name "P_ADD09") (class "Default")
      (node (ref "A23") (pin "D2") (pinfunction "P$2_D2") (pintype "bidirectional"))
      (node (ref "B19") (pin "P2") (pinfunction "IN_P2") (pintype "input"))
      (node (ref "B21") (pin "S2") (pinfunction "P$1_S2") (pintype "passive"))
    )
    (net (code "118") (name "P_ADD10") (class "Default")
      (node (ref "A23") (pin "E2") (pinfunction "P$2_E2") (pintype "bidirectional"))
      (node (ref "B19") (pin "R2") (pinfunction "IN_R2") (pintype "input"))
      (node (ref "B21") (pin "T2") (pinfunction "P$1_T2") (pintype "passive"))
    )
    (net (code "119") (name "P_ADD11") (class "Default")
      (node (ref "A23") (pin "H2") (pinfunction "P$2_H2") (pintype "bidirectional"))
      (node (ref "B19") (pin "S2") (pinfunction "IN_S2") (pintype "input"))
      (node (ref "B21") (pin "V2") (pinfunction "P$1_V2") (pintype "passive"))
    )
    (net (code "120") (name "P_BAC00") (class "Default")
      (node (ref "A20") (pin "B1") (pinfunction "P$2_B1") (pintype "bidirectional"))
      (node (ref "B12") (pin "D2") (pinfunction "OUT_D2") (pintype "output"))
      (node (ref "B15") (pin "D1") (pinfunction "P$1_D1") (pintype "passive"))
    )
    (net (code "121") (name "P_BAC01") (class "Default")
      (node (ref "A20") (pin "D1") (pinfunction "P$2_D1") (pintype "bidirectional"))
      (node (ref "B12") (pin "F2") (pinfunction "OUT_F2") (pintype "output"))
      (node (ref "B15") (pin "E1") (pinfunction "P$1_E1") (pintype "passive"))
    )
    (net (code "122") (name "P_BAC02") (class "Default")
      (node (ref "A20") (pin "E1") (pinfunction "P$2_E1") (pintype "bidirectional"))
      (node (ref "B12") (pin "J2") (pinfunction "OUT_J2") (pintype "output"))
      (node (ref "B15") (pin "H1") (pinfunction "P$1_H1") (pintype "passive"))
    )
    (net (code "123") (name "P_BAC03") (class "Default")
      (node (ref "A20") (pin "H1") (pinfunction "P$2_H1") (pintype "bidirectional"))
      (node (ref "B12") (pin "L2") (pinfunction "OUT_L2") (pintype "output"))
      (node (ref "B15") (pin "J1") (pinfunction "P$1_J1") (pintype "passive"))
    )
    (net (code "124") (name "P_BAC04") (class "Default")
      (node (ref "A20") (pin "J1") (pinfunction "P$2_J1") (pintype "bidirectional"))
      (node (ref "B12") (pin "N2") (pinfunction "OUT_N2") (pintype "output"))
      (node (ref "B15") (pin "L1") (pinfunction "P$1_L1") (pintype "passive"))
    )
    (net (code "125") (name "P_BAC05") (class "Default")
      (node (ref "A20") (pin "L1") (pinfunction "P$2_L1") (pintype "bidirectional"))
      (node (ref "B12") (pin "R2") (pinfunction "OUT_R2") (pintype "output"))
      (node (ref "B15") (pin "M1") (pinfunction "P$1_M1") (pintype "passive"))
    )
    (net (code "126") (name "P_BAC06") (class "Default")
      (node (ref "A20") (pin "M1") (pinfunction "P$2_M1") (pintype "bidirectional"))
      (node (ref "B13") (pin "D2") (pinfunction "OUT_D2") (pintype "output"))
      (node (ref "B15") (pin "P1") (pinfunction "P$1_P1") (pintype "passive"))
    )
    (net (code "127") (name "P_BAC07") (class "Default")
      (node (ref "A20") (pin "P1") (pinfunction "P$2_P1") (pintype "bidirectional"))
      (node (ref "B13") (pin "F2") (pinfunction "OUT_F2") (pintype "output"))
      (node (ref "B15") (pin "S1") (pinfunction "P$1_S1") (pintype "passive"))
    )
    (net (code "128") (name "P_BAC08") (class "Default")
      (node (ref "A20") (pin "S1") (pinfunction "P$2_S1") (pintype "bidirectional"))
      (node (ref "B13") (pin "J2") (pinfunction "OUT_J2") (pintype "output"))
      (node (ref "B15") (pin "D2") (pinfunction "P$1_D2") (pintype "passive"))
    )
    (net (code "129") (name "P_BAC09") (class "Default")
      (node (ref "A20") (pin "D2") (pinfunction "P$2_D2") (pintype "bidirectional"))
      (node (ref "B13") (pin "L2") (pinfunction "OUT_L2") (pintype "output"))
      (node (ref "B15") (pin "E2") (pinfunction "P$1_E2") (pintype "passive"))
    )
    (net (code "130") (name "P_BAC10") (class "Default")
      (node (ref "A20") (pin "E2") (pinfunction "P$2_E2") (pintype "bidirectional"))
      (node (ref "B13") (pin "N2") (pinfunction "OUT_N2") (pintype "output"))
      (node (ref "B15") (pin "H2") (pinfunction "P$1_H2") (pintype "passive"))
    )
    (net (code "131") (name "P_BAC11") (class "Default")
      (node (ref "A20") (pin "H2") (pinfunction "P$2_H2") (pintype "bidirectional"))
      (node (ref "B13") (pin "R2") (pinfunction "OUT_R2") (pintype "output"))
      (node (ref "B15") (pin "K2") (pinfunction "P$1_K2") (pintype "passive"))
    )
    (net (code "132") (name "P_BREAK") (class "Default")
      (node (ref "A23") (pin "P2") (pinfunction "P$2_P2") (pintype "bidirectional"))
      (node (ref "B14") (pin "J2") (pinfunction "OUT_J2") (pintype "output"))
      (node (ref "B15") (pin "S2") (pinfunction "P$1_S2") (pintype "passive"))
    )
    (net (code "133") (name "P_BRKRQ") (class "Default")
      (node (ref "A17") (pin "B1") (pinfunction "P$1_B1") (pintype "passive"))
      (node (ref "A23") (pin "K2") (pinfunction "P$2_K2") (pintype "bidirectional"))
      (node (ref "B17") (pin "J2") (pinfunction "IN_J2") (pintype "input"))
    )
    (net (code "134") (name "P_CAINCR") (class "Default")
      (node (ref "A17") (pin "J1") (pinfunction "P$1_J1") (pintype "passive"))
      (node (ref "A24") (pin "M2") (pinfunction "P$2_M2") (pintype "bidirectional"))
      (node (ref "B17") (pin "N2") (pinfunction "IN_N2") (pintype "input"))
    )
    (net (code "135") (name "P_DATA00") (class "Default")
      (node (ref "A24") (pin "B1") (pinfunction "P$2_B1") (pintype "bidirectional"))
      (node (ref "B20") (pin "D2") (pinfunction "IN_D2") (pintype "input"))
      (node (ref "B21") (pin "B1") (pinfunction "P$1_B1") (pintype "passive"))
    )
    (net (code "136") (name "P_DATA01") (class "Default")
      (node (ref "A24") (pin "D1") (pinfunction "P$2_D1") (pintype "bidirectional"))
      (node (ref "B20") (pin "E2") (pinfunction "IN_E2") (pintype "input"))
      (node (ref "B21") (pin "D1") (pinfunction "P$1_D1") (pintype "passive"))
    )
    (net (code "137") (name "P_DATA02") (class "Default")
      (node (ref "A24") (pin "E1") (pinfunction "P$2_E1") (pintype "bidirectional"))
      (node (ref "B20") (pin "F2") (pinfunction "IN_F2") (pintype "input"))
      (node (ref "B21") (pin "E1") (pinfunction "P$1_E1") (pintype "passive"))
    )
    (net (code "138") (name "P_DATA03") (class "Default")
      (node (ref "A24") (pin "H1") (pinfunction "P$2_H1") (pintype "bidirectional"))
      (node (ref "B20") (pin "H2") (pinfunction "IN_H2") (pintype "input"))
      (node (ref "B21") (pin "H1") (pinfunction "P$1_H1") (pintype "passive"))
    )
    (net (code "139") (name "P_DATA04") (class "Default")
      (node (ref "A24") (pin "J1") (pinfunction "P$2_J1") (pintype "bidirectional"))
      (node (ref "B20") (pin "J2") (pinfunction "IN_J2") (pintype "input"))
      (node (ref "B21") (pin "J1") (pinfunction "P$1_J1") (pintype "passive"))
    )
    (net (code "140") (name "P_DATA05") (class "Default")
      (node (ref "A24") (pin "L1") (pinfunction "P$2_L1") (pintype "bidirectional"))
      (node (ref "B20") (pin "K2") (pinfunction "IN_K2") (pintype "input"))
      (node (ref "B21") (pin "L1") (pinfunction "P$1_L1") (pintype "passive"))
    )
    (net (code "141") (name "P_DATA06") (class "Default")
      (node (ref "A24") (pin "M1") (pinfunction "P$2_M1") (pintype "bidirectional"))
      (node (ref "B20") (pin "L2") (pinfunction "IN_L2") (pintype "input"))
      (node (ref "B21") (pin "M1") (pinfunction "P$1_M1") (pintype "passive"))
    )
    (net (code "142") (name "P_DATA07") (class "Default")
      (node (ref "A24") (pin "P1") (pinfunction "P$2_P1") (pintype "bidirectional"))
      (node (ref "B20") (pin "M2") (pinfunction "IN_M2") (pintype "input"))
      (node (ref "B21") (pin "P1") (pinfunction "P$1_P1") (pintype "passive"))
    )
    (net (code "143") (name "P_DATA08") (class "Default")
      (node (ref "A24") (pin "S1") (pinfunction "P$2_S1") (pintype "bidirectional"))
      (node (ref "B20") (pin "N2") (pinfunction "IN_N2") (pintype "input"))
      (node (ref "B21") (pin "S1") (pinfunction "P$1_S1") (pintype "passive"))
    )
    (net (code "144") (name "P_DATA09") (class "Default")
      (node (ref "A24") (pin "D2") (pinfunction "P$2_D2") (pintype "bidirectional"))
      (node (ref "B20") (pin "P2") (pinfunction "IN_P2") (pintype "input"))
      (node (ref "B21") (pin "D2") (pinfunction "P$1_D2") (pintype "passive"))
    )
    (net (code "145") (name "P_DATA10") (class "Default")
      (node (ref "A24") (pin "E2") (pinfunction "P$2_E2") (pintype "bidirectional"))
      (node (ref "B20") (pin "R2") (pinfunction "IN_R2") (pintype "input"))
      (node (ref "B21") (pin "E2") (pinfunction "P$1_E2") (pintype "passive"))
    )
    (net (code "146") (name "P_DATA11") (class "Default")
      (node (ref "A24") (pin "H2") (pinfunction "P$2_H2") (pintype "bidirectional"))
      (node (ref "B20") (pin "S2") (pinfunction "IN_S2") (pintype "input"))
      (node (ref "B21") (pin "H2") (pinfunction "P$1_H2") (pintype "passive"))
    )
    (net (code "147") (name "P_DATAIN") (class "Default")
      (node (ref "A17") (pin "D1") (pinfunction "P$1_D1") (pintype "passive"))
      (node (ref "A23") (pin "M2") (pinfunction "P$2_M2") (pintype "bidirectional"))
      (node (ref "B17") (pin "K2") (pinfunction "IN_K2") (pintype "input"))
    )
    (net (code "148") (name "P_EXTA0") (class "Default")
      (node (ref "A17") (pin "P1") (pinfunction "P$1_P1") (pintype "passive"))
      (node (ref "A24") (pin "V2") (pinfunction "P$2_V2") (pintype "bidirectional"))
      (node (ref "B17") (pin "S2") (pinfunction "IN_S2") (pintype "input"))
    )
    (net (code "149") (name "P_EXTA1") (class "Default")
      (node (ref "A17") (pin "M1") (pinfunction "P$1_M1") (pintype "passive"))
      (node (ref "A24") (pin "T2") (pinfunction "P$2_T2") (pintype "bidirectional"))
      (node (ref "B17") (pin "R2") (pinfunction "IN_R2") (pintype "input"))
    )
    (net (code "150") (name "P_EXTA2") (class "Default")
      (node (ref "A17") (pin "L1") (pinfunction "P$1_L1") (pintype "passive"))
      (node (ref "A24") (pin "S2") (pinfunction "P$2_S2") (pintype "bidirectional"))
      (node (ref "B17") (pin "P2") (pinfunction "IN_P2") (pintype "input"))
    )
    (net (code "151") (name "P_INIT") (class "Default")
      (node (ref "A19") (pin "S2") (pinfunction "OUT_S2") (pintype "output"))
      (node (ref "A20") (pin "V2") (pinfunction "P$2_V2") (pintype "bidirectional"))
      (node (ref "A23") (pin "V2") (pinfunction "P$2_V2") (pintype "bidirectional"))
    )
    (net (code "152") (name "P_IOP1") (class "Default")
      (node (ref "A18") (pin "D2") (pinfunction "OUT_D2") (pintype "output"))
      (node (ref "A20") (pin "K2") (pinfunction "P$2_K2") (pintype "bidirectional"))
    )
    (net (code "153") (name "P_IOP2") (class "Default")
      (node (ref "A18") (pin "K2") (pinfunction "OUT_K2") (pintype "output"))
      (node (ref "A20") (pin "M2") (pinfunction "P$2_M2") (pintype "bidirectional"))
    )
    (net (code "154") (name "P_IOP4") (class "Default")
      (node (ref "A18") (pin "S2") (pinfunction "OUT_S2") (pintype "output"))
      (node (ref "A20") (pin "P2") (pinfunction "P$2_P2") (pintype "bidirectional"))
    )
    (net (code "155") (name "P_IRQ") (class "Default")
      (node (ref "A22") (pin "M2") (pinfunction "P$2_M2") (pintype "bidirectional"))
      (node (ref "B17") (pin "E2") (pinfunction "IN_E2") (pintype "input"))
      (node (ref "B18") (pin "M2") (pinfunction "P$1_M2") (pintype "passive"))
    )
    (net (code "156") (name "P_LINE") (class "Default")
      (node (ref "A22") (pin "V2") (pinfunction "P$2_V2") (pintype "bidirectional"))
      (node (ref "B17") (pin "H2") (pinfunction "IN_H2") (pintype "input"))
      (node (ref "B18") (pin "S2") (pinfunction "P$1_S2") (pintype "passive"))
    )
    (net (code "157") (name "P_MB00") (class "Default")
      (node (ref "A12") (pin "D2") (pinfunction "OUT_D2") (pintype "output"))
      (node (ref "A15") (pin "B1") (pinfunction "P$1_B1") (pintype "passive"))
      (node (ref "A21") (pin "B1") (pinfunction "P$2_B1") (pintype "bidirectional"))
    )
    (net (code "158") (name "P_MB01") (class "Default")
      (node (ref "A12") (pin "F2") (pinfunction "OUT_F2") (pintype "output"))
      (node (ref "A15") (pin "D1") (pinfunction "P$1_D1") (pintype "passive"))
      (node (ref "A21") (pin "D1") (pinfunction "P$2_D1") (pintype "bidirectional"))
    )
    (net (code "159") (name "P_MB02") (class "Default")
      (node (ref "A12") (pin "J2") (pinfunction "OUT_J2") (pintype "output"))
      (node (ref "A15") (pin "E1") (pinfunction "P$1_E1") (pintype "passive"))
      (node (ref "A21") (pin "E1") (pinfunction "P$2_E1") (pintype "bidirectional"))
    )
    (net (code "160") (name "P_MB03") (class "Default")
      (node (ref "A12") (pin "N2") (pinfunction "OUT_N2") (pintype "output"))
      (node (ref "A15") (pin "J1") (pinfunction "P$1_J1") (pintype "passive"))
      (node (ref "A21") (pin "J1") (pinfunction "P$2_J1") (pintype "bidirectional"))
    )
    (net (code "161") (name "P_MB04") (class "Default")
      (node (ref "A13") (pin "D2") (pinfunction "OUT_D2") (pintype "output"))
      (node (ref "A15") (pin "M1") (pinfunction "P$1_M1") (pintype "passive"))
      (node (ref "A21") (pin "M1") (pinfunction "P$2_M1") (pintype "bidirectional"))
    )
    (net (code "162") (name "P_MB05") (class "Default")
      (node (ref "A13") (pin "J2") (pinfunction "OUT_J2") (pintype "output"))
      (node (ref "A15") (pin "S1") (pinfunction "P$1_S1") (pintype "passive"))
      (node (ref "A21") (pin "S1") (pinfunction "P$2_S1") (pintype "bidirectional"))
    )
    (net (code "163") (name "P_MB06") (class "Default")
      (node (ref "A13") (pin "N2") (pinfunction "OUT_N2") (pintype "output"))
      (node (ref "A15") (pin "E2") (pinfunction "P$1_E2") (pintype "passive"))
      (node (ref "A21") (pin "E2") (pinfunction "P$2_E2") (pintype "bidirectional"))
    )
    (net (code "164") (name "P_MB07") (class "Default")
      (node (ref "A14") (pin "D2") (pinfunction "OUT_D2") (pintype "output"))
      (node (ref "A15") (pin "K2") (pinfunction "P$1_K2") (pintype "passive"))
      (node (ref "A21") (pin "K2") (pinfunction "P$2_K2") (pintype "bidirectional"))
    )
    (net (code "165") (name "P_MB08") (class "Default")
      (node (ref "A14") (pin "J2") (pinfunction "OUT_J2") (pintype "output"))
      (node (ref "A15") (pin "P2") (pinfunction "P$1_P2") (pintype "passive"))
      (node (ref "A21") (pin "P2") (pinfunction "P$2_P2") (pintype "bidirectional"))
    )
    (net (code "166") (name "P_MB09") (class "Default")
      (node (ref "A14") (pin "L2") (pinfunction "OUT_L2") (pintype "output"))
      (node (ref "A15") (pin "S2") (pinfunction "P$1_S2") (pintype "passive"))
      (node (ref "A21") (pin "S2") (pinfunction "P$2_S2") (pintype "bidirectional"))
    )
    (net (code "167") (name "P_MB10") (class "Default")
      (node (ref "A14") (pin "N2") (pinfunction "OUT_N2") (pintype "output"))
      (node (ref "A15") (pin "T2") (pinfunction "P$1_T2") (pintype "passive"))
      (node (ref "A21") (pin "T2") (pinfunction "P$2_T2") (pintype "bidirectional"))
    )
    (net (code "168") (name "P_MB11") (class "Default")
      (node (ref "A14") (pin "R2") (pinfunction "OUT_R2") (pintype "output"))
      (node (ref "A15") (pin "V2") (pinfunction "P$1_V2") (pintype "passive"))
      (node (ref "A21") (pin "V2") (pinfunction "P$2_V2") (pintype "bidirectional"))
    )
    (net (code "169") (name "P_MBINCR") (class "Default")
      (node (ref "A17") (pin "E1") (pinfunction "P$1_E1") (pintype "passive"))
      (node (ref "A23") (pin "T2") (pinfunction "P$2_T2") (pintype "bidirectional"))
      (node (ref "B17") (pin "L2") (pinfunction "IN_L2") (pintype "input"))
    )
    (net (code "170") (name "P_RUN") (class "Default")
      (node (ref "A22") (pin "S2") (pinfunction "P$2_S2") (pintype "bidirectional"))
      (node (ref "B14") (pin "D2") (pinfunction "OUT_D2") (pintype "output"))
      (node (ref "B15") (pin "M2") (pinfunction "P$1_M2") (pintype "passive"))
    )
    (net (code "171") (name "P_SKIP") (class "Default")
      (node (ref "A22") (pin "K2") (pinfunction "P$2_K2") (pintype "bidirectional"))
      (node (ref "B17") (pin "D2") (pinfunction "IN_D2") (pintype "input"))
      (node (ref "B18") (pin "K2") (pinfunction "P$1_K2") (pintype "passive"))
    )
    (net (code "172") (name "P_TS1") (class "Default")
      (node (ref "A19") (pin "K2") (pinfunction "OUT_K2") (pintype "output"))
      (node (ref "A20") (pin "T2") (pinfunction "P$2_T2") (pintype "bidirectional"))
    )
    (net (code "173") (name "P_TS3") (class "Default")
      (node (ref "A19") (pin "D2") (pinfunction "OUT_D2") (pintype "output"))
      (node (ref "A20") (pin "S2") (pinfunction "P$2_S2") (pintype "bidirectional"))
    )
    (net (code "174") (name "P_TT_INST") (class "Default")
      (node (ref "A22") (pin "T2") (pinfunction "P$2_T2") (pintype "bidirectional"))
      (node (ref "B14") (pin "F2") (pinfunction "OUT_F2") (pintype "output"))
      (node (ref "B15") (pin "P2") (pinfunction "P$1_P2") (pintype "passive"))
    )
    (net (code "175") (name "P_WCOV") (class "Default")
      (node (ref "A24") (pin "P2") (pinfunction "P$2_P2") (pintype "bidirectional"))
      (node (ref "B14") (pin "N2") (pinfunction "OUT_N2") (pintype "output"))
      (node (ref "B15") (pin "V2") (pinfunction "P$1_V2") (pintype "passive"))
    )
    (net (code "177") (name "~{N_MB03}") (class "Default")
      (node (ref "A03") (pin "K2") (pinfunction "P$2_K2") (pintype "bidirectional"))
      (node (ref "A12") (pin "M2") (pinfunction "IN_M2") (pintype "input"))
      (node (ref "B03") (pin "K2") (pinfunction "P$2_K2") (pintype "bidirectional"))
    )
    (net (code "178") (name "~{N_MB04}") (class "Default")
      (node (ref "A03") (pin "P2") (pinfunction "P$2_P2") (pintype "bidirectional"))
      (node (ref "A12") (pin "S2") (pinfunction "IN_S2") (pintype "input"))
      (node (ref "B03") (pin "P2") (pinfunction "P$2_P2") (pintype "bidirectional"))
    )
    (net (code "179") (name "~{N_MB05}") (class "Default")
      (node (ref "A03") (pin "T2") (pinfunction "P$2_T2") (pintype "bidirectional"))
      (node (ref "A13") (pin "H2") (pinfunction "IN_H2") (pintype "input"))
      (node (ref "B03") (pin "T2") (pinfunction "P$2_T2") (pintype "bidirectional"))
    )
    (net (code "180") (name "~{N_MB06}") (class "Default")
      (node (ref "A04") (pin "D2") (pinfunction "P$2_D2") (pintype "bidirectional"))
      (node (ref "A13") (pin "M2") (pinfunction "IN_M2") (pintype "input"))
      (node (ref "B04") (pin "D2") (pinfunction "P$2_D2") (pintype "bidirectional"))
    )
    (net (code "181") (name "~{N_MB07}") (class "Default")
      (node (ref "A04") (pin "H2") (pinfunction "P$2_H2") (pintype "bidirectional"))
      (node (ref "A13") (pin "S2") (pinfunction "IN_S2") (pintype "input"))
      (node (ref "B04") (pin "H2") (pinfunction "P$2_H2") (pintype "bidirectional"))
    )
    (net (code "182") (name "~{N_MB08}") (class "Default")
      (node (ref "A04") (pin "M2") (pinfunction "P$2_M2") (pintype "bidirectional"))
      (node (ref "A14") (pin "H2") (pinfunction "IN_H2") (pintype "input"))
      (node (ref "B04") (pin "M2") (pinfunction "P$2_M2") (pintype "bidirectional"))
    )
    (net (code "183") (name "~{P_MB03}") (class "Default")
      (node (ref "A12") (pin "L2") (pinfunction "OUT_L2") (pintype "output"))
      (node (ref "A15") (pin "H1") (pinfunction "P$1_H1") (pintype "passive"))
      (node (ref "A21") (pin "H1") (pinfunction "P$2_H1") (pintype "bidirectional"))
    )
    (net (code "184") (name "~{P_MB04}") (class "Default")
      (node (ref "A12") (pin "R2") (pinfunction "OUT_R2") (pintype "output"))
      (node (ref "A15") (pin "L1") (pinfunction "P$1_L1") (pintype "passive"))
      (node (ref "A21") (pin "L1") (pinfunction "P$2_L1") (pintype "bidirectional"))
    )
    (net (code "185") (name "~{P_MB05}") (class "Default")
      (node (ref "A13") (pin "F2") (pinfunction "OUT_F2") (pintype "output"))
      (node (ref "A15") (pin "P1") (pinfunction "P$1_P1") (pintype "passive"))
      (node (ref "A21") (pin "P1") (pinfunction "P$2_P1") (pintype "bidirectional"))
    )
    (net (code "186") (name "~{P_MB06}") (class "Default")
      (node (ref "A13") (pin "L2") (pinfunction "OUT_L2") (pintype "output"))
      (node (ref "A15") (pin "D2") (pinfunction "P$1_D2") (pintype "passive"))
      (node (ref "A21") (pin "D2") (pinfunction "P$2_D2") (pintype "bidirectional"))
    )
    (net (code "187") (name "~{P_MB07}") (class "Default")
      (node (ref "A13") (pin "R2") (pinfunction "OUT_R2") (pintype "output"))
      (node (ref "A15") (pin "H2") (pinfunction "P$1_H2") (pintype "passive"))
      (node (ref "A21") (pin "H2") (pinfunction "P$2_H2") (pintype "bidirectional"))
    )
    (net (code "188") (name "~{P_MB08}") (class "Default")
      (node (ref "A14") (pin "F2") (pinfunction "OUT_F2") (pintype "output"))
      (node (ref "A15") (pin "M2") (pinfunction "P$1_M2") (pintype "passive"))
      (node (ref "A21") (pin "M2") (pinfunction "P$2_M2") (pintype "bidirectional"))
    )
  )
)
